# SCH_Octoslime_2022-08-10_Schematics.net
KiCad netlist of a schematic drawn in EasyEDA
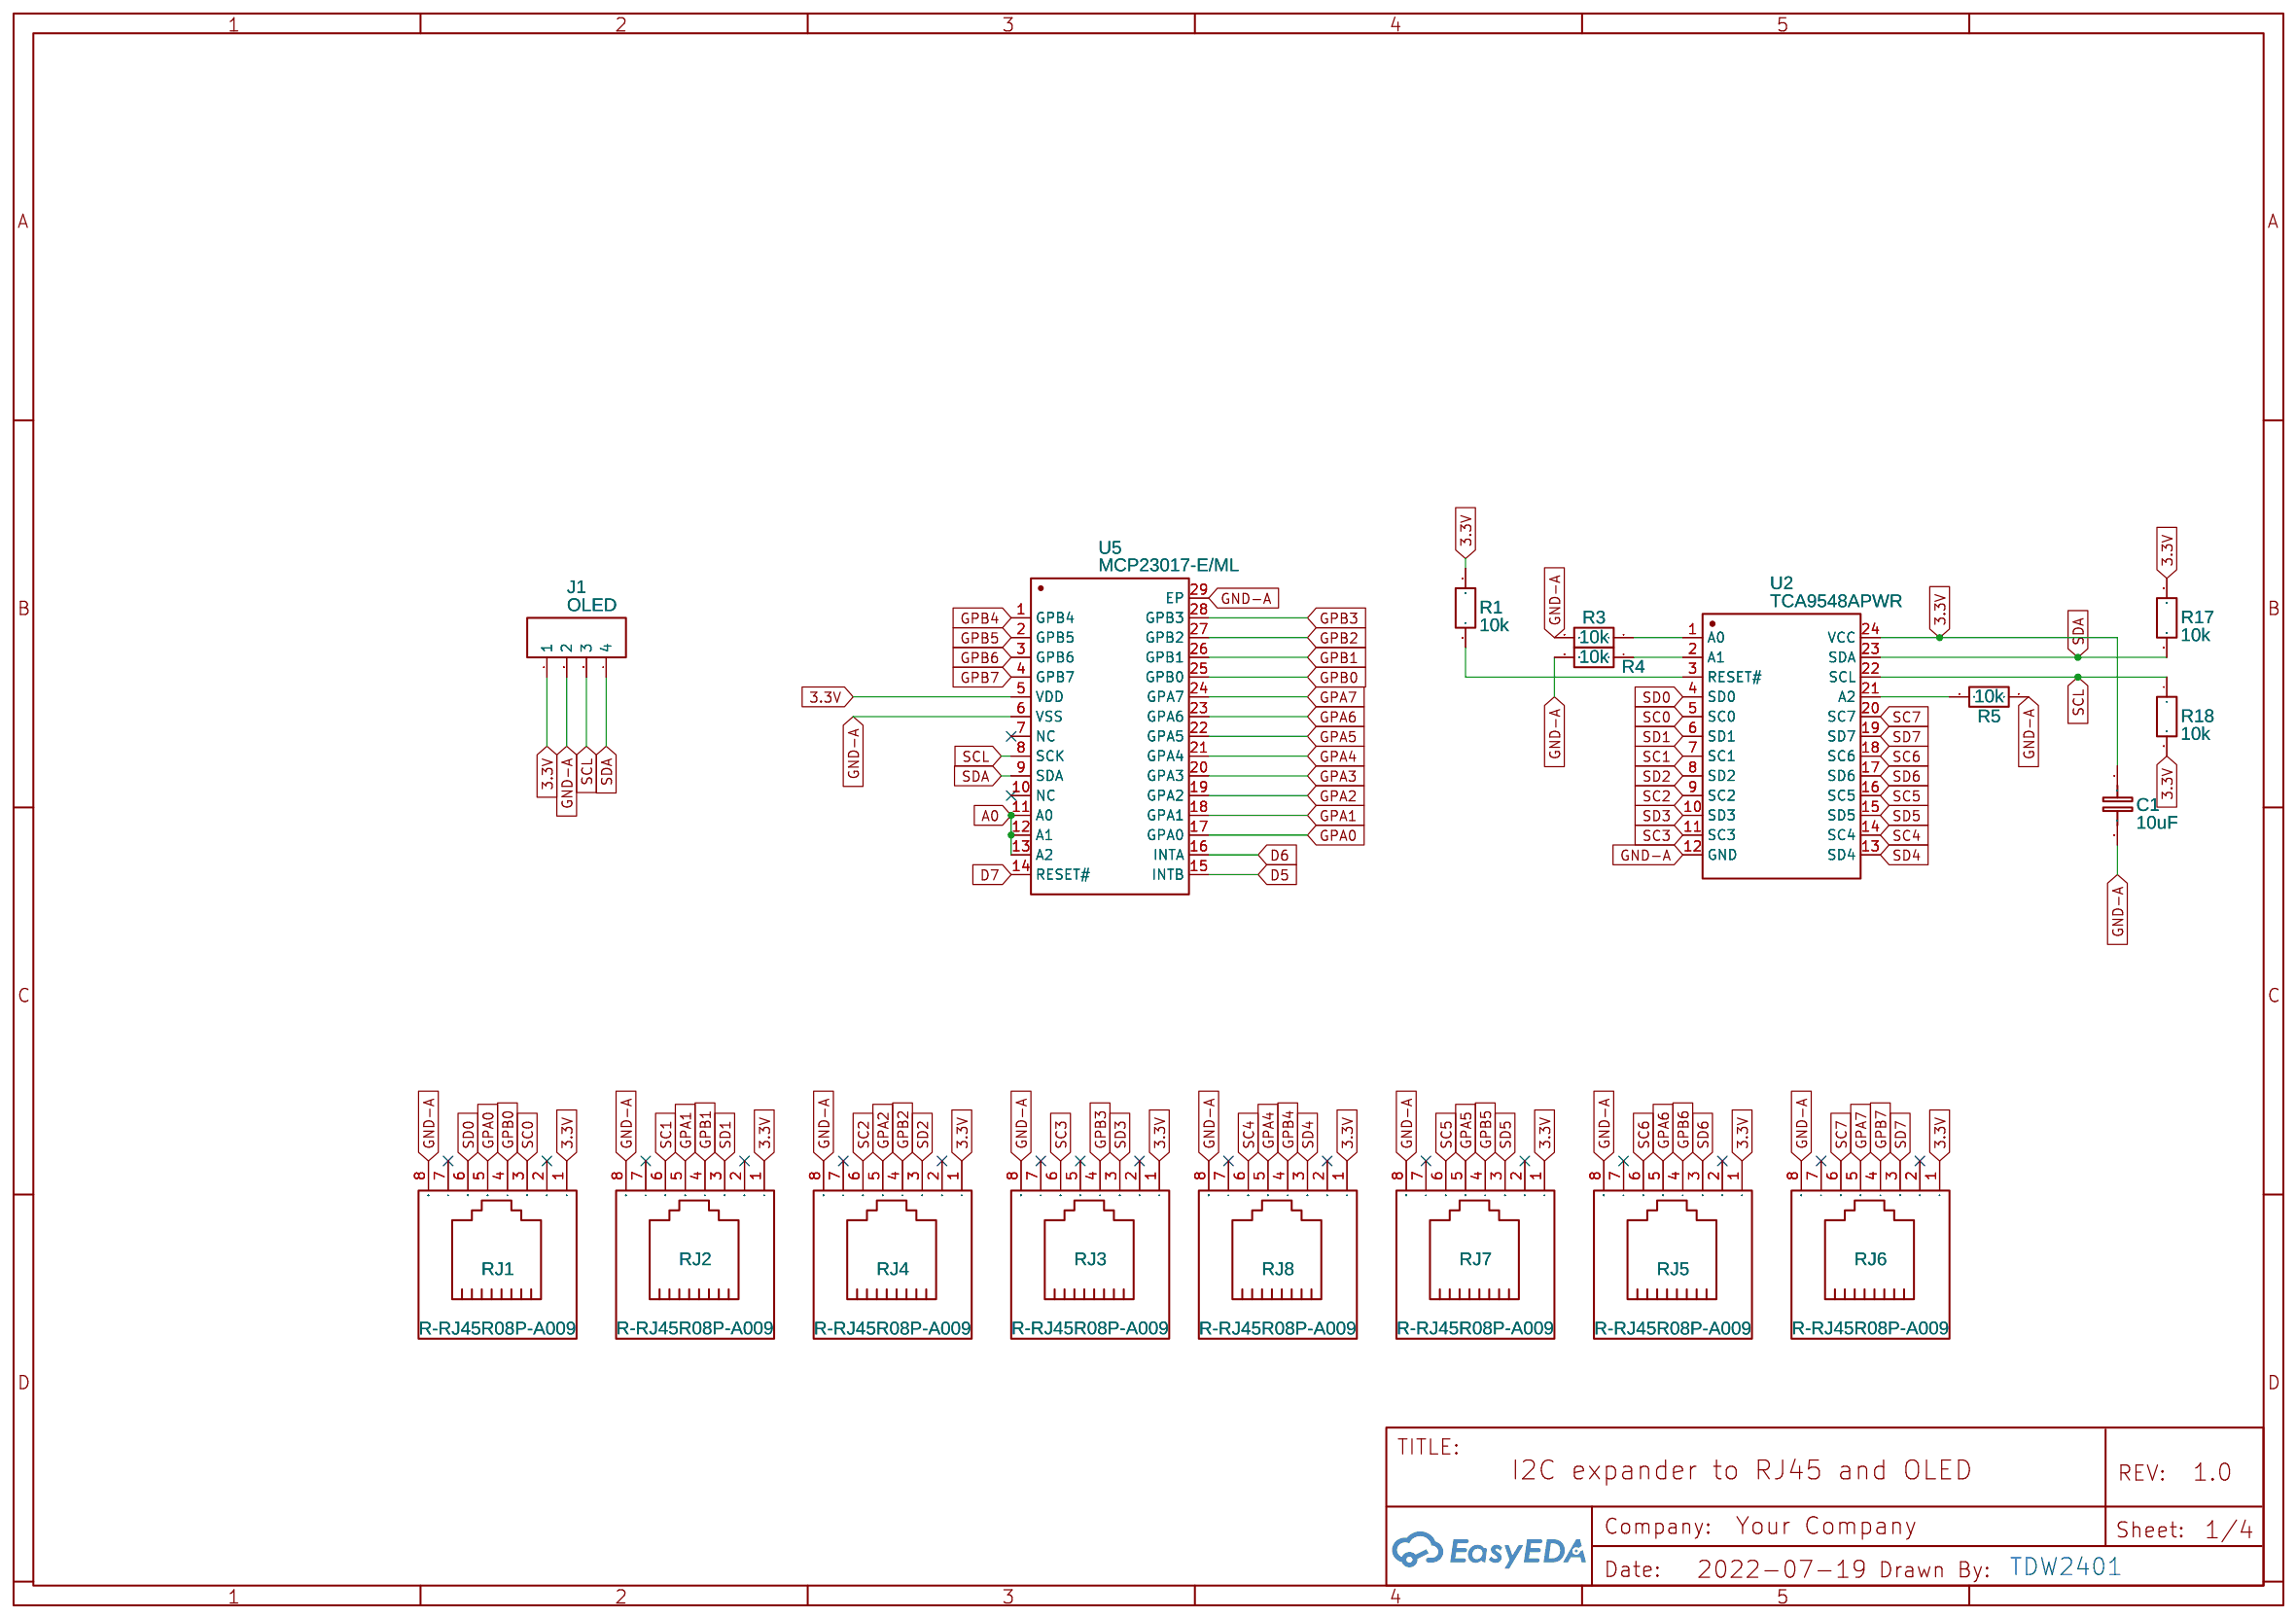
[diagram p0: I2C breakout and OLED]
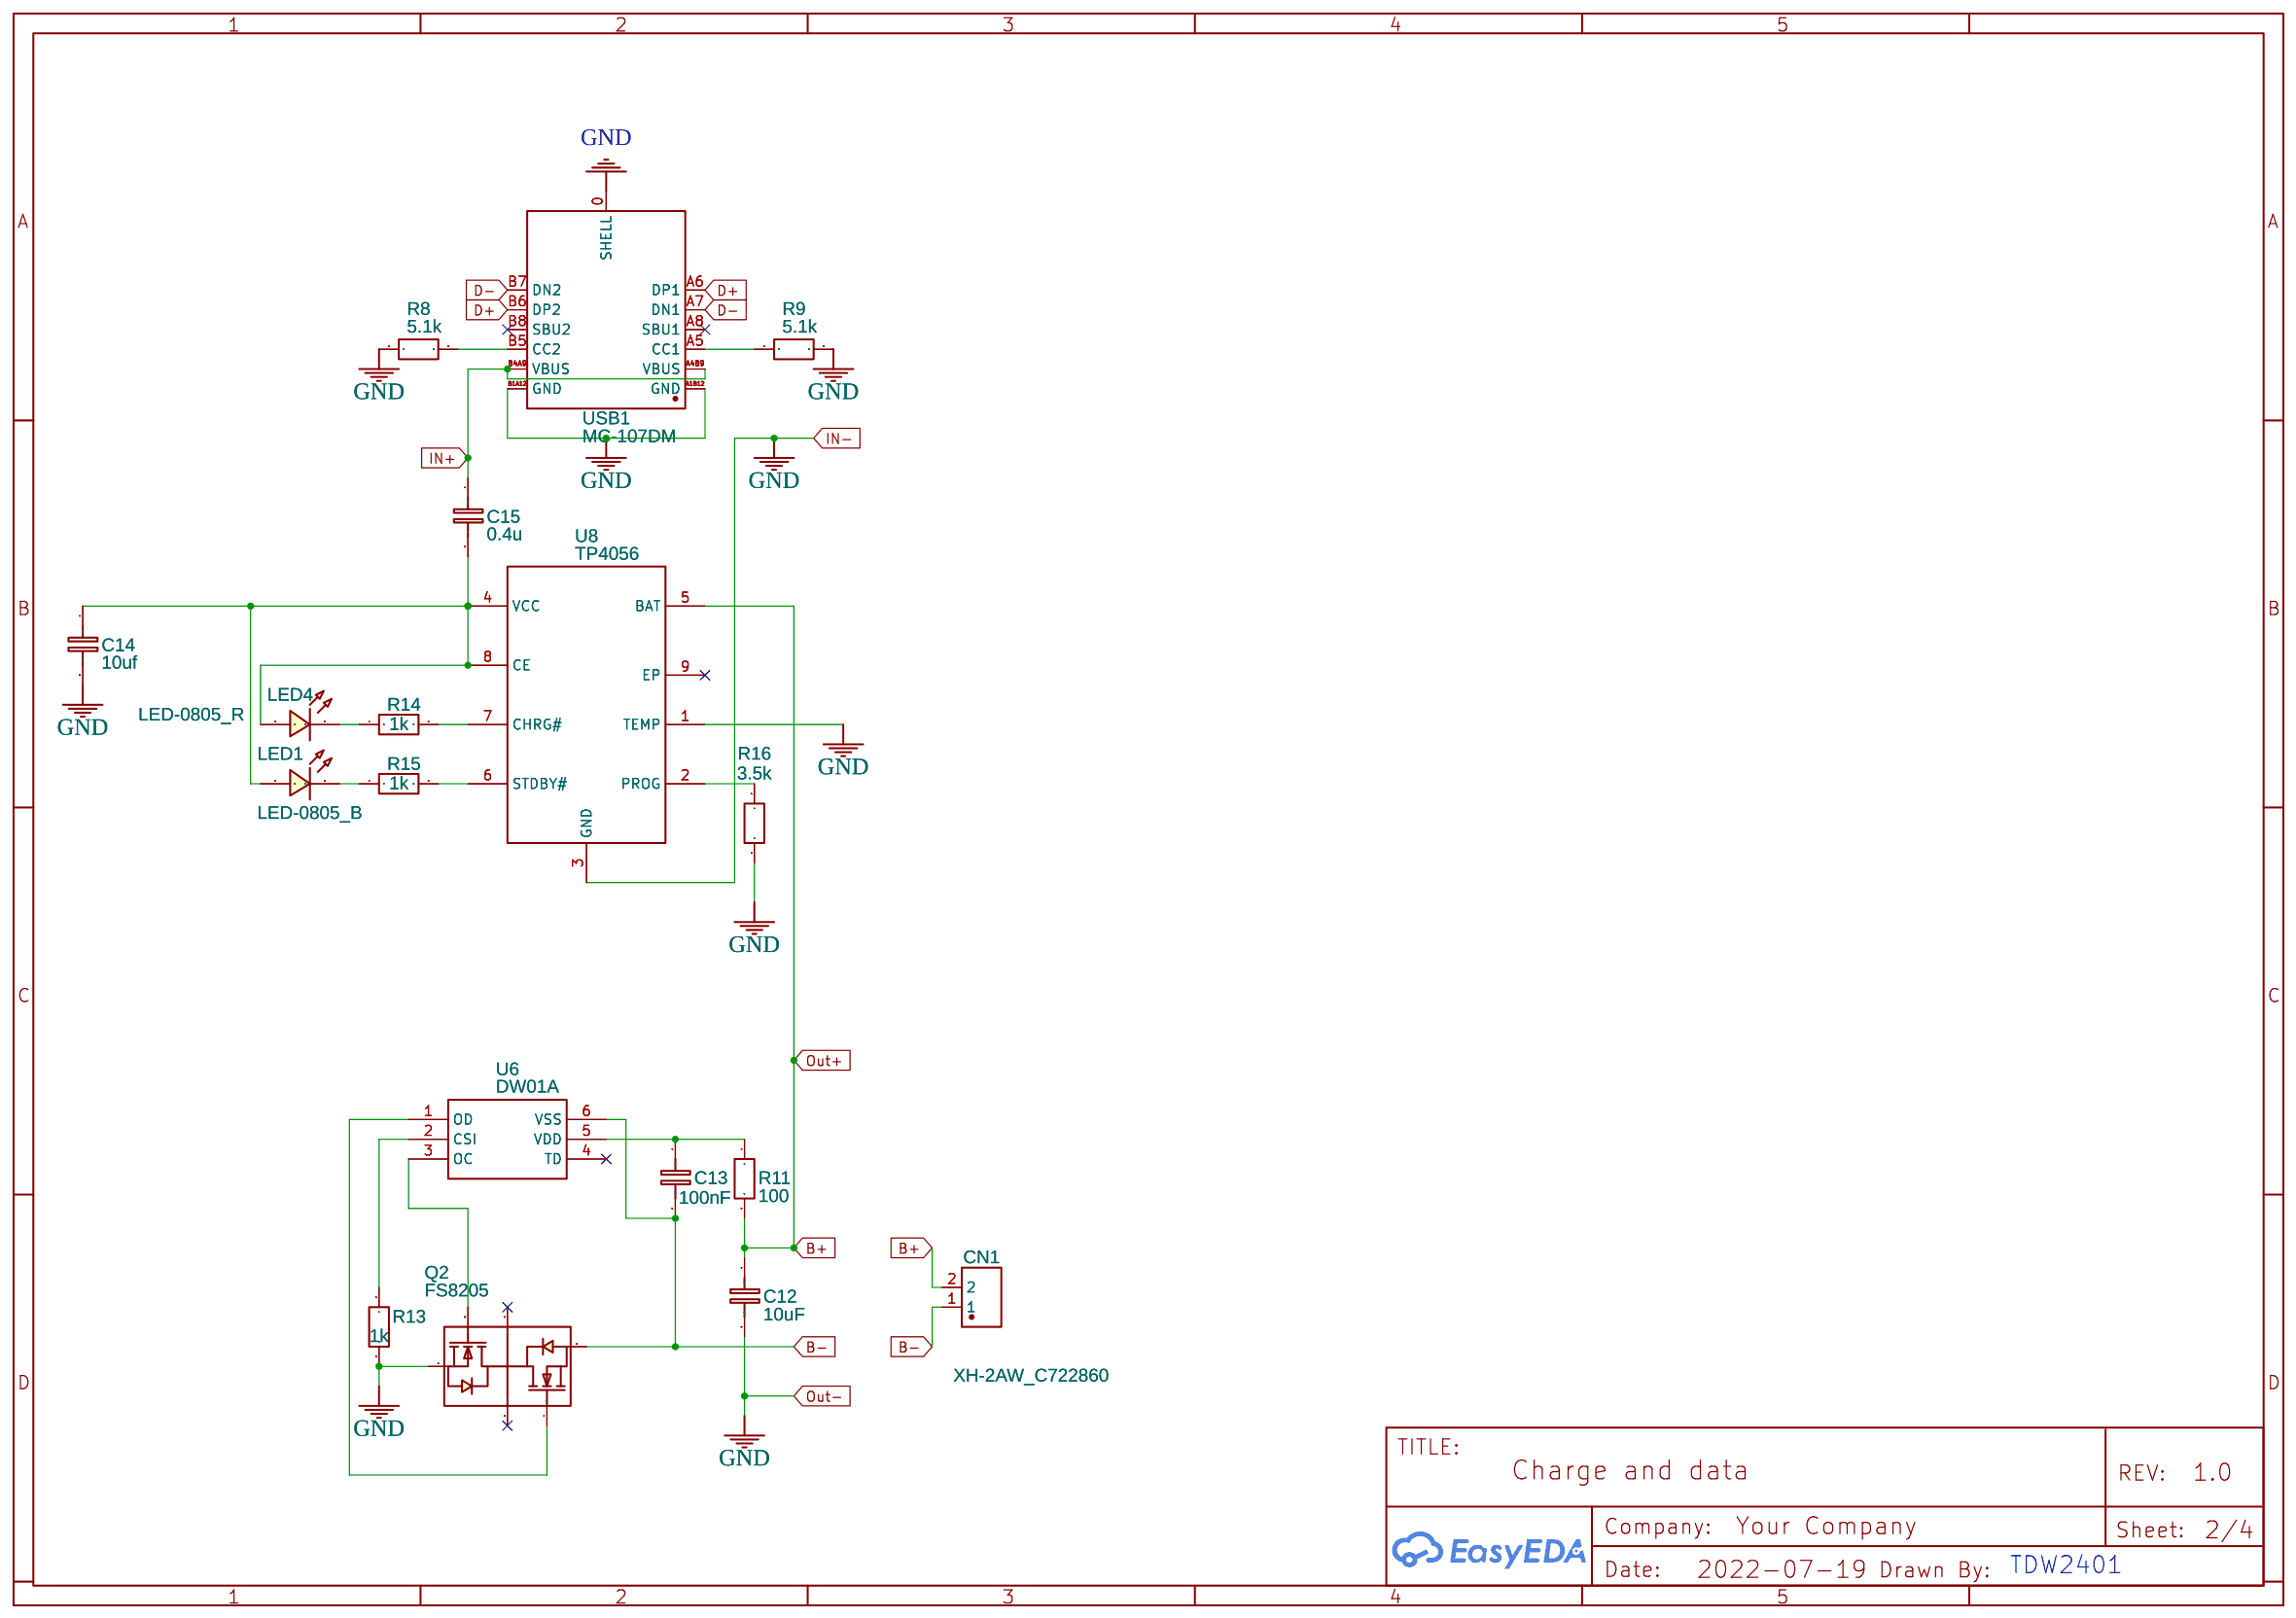
[diagram p1: Charge / data]
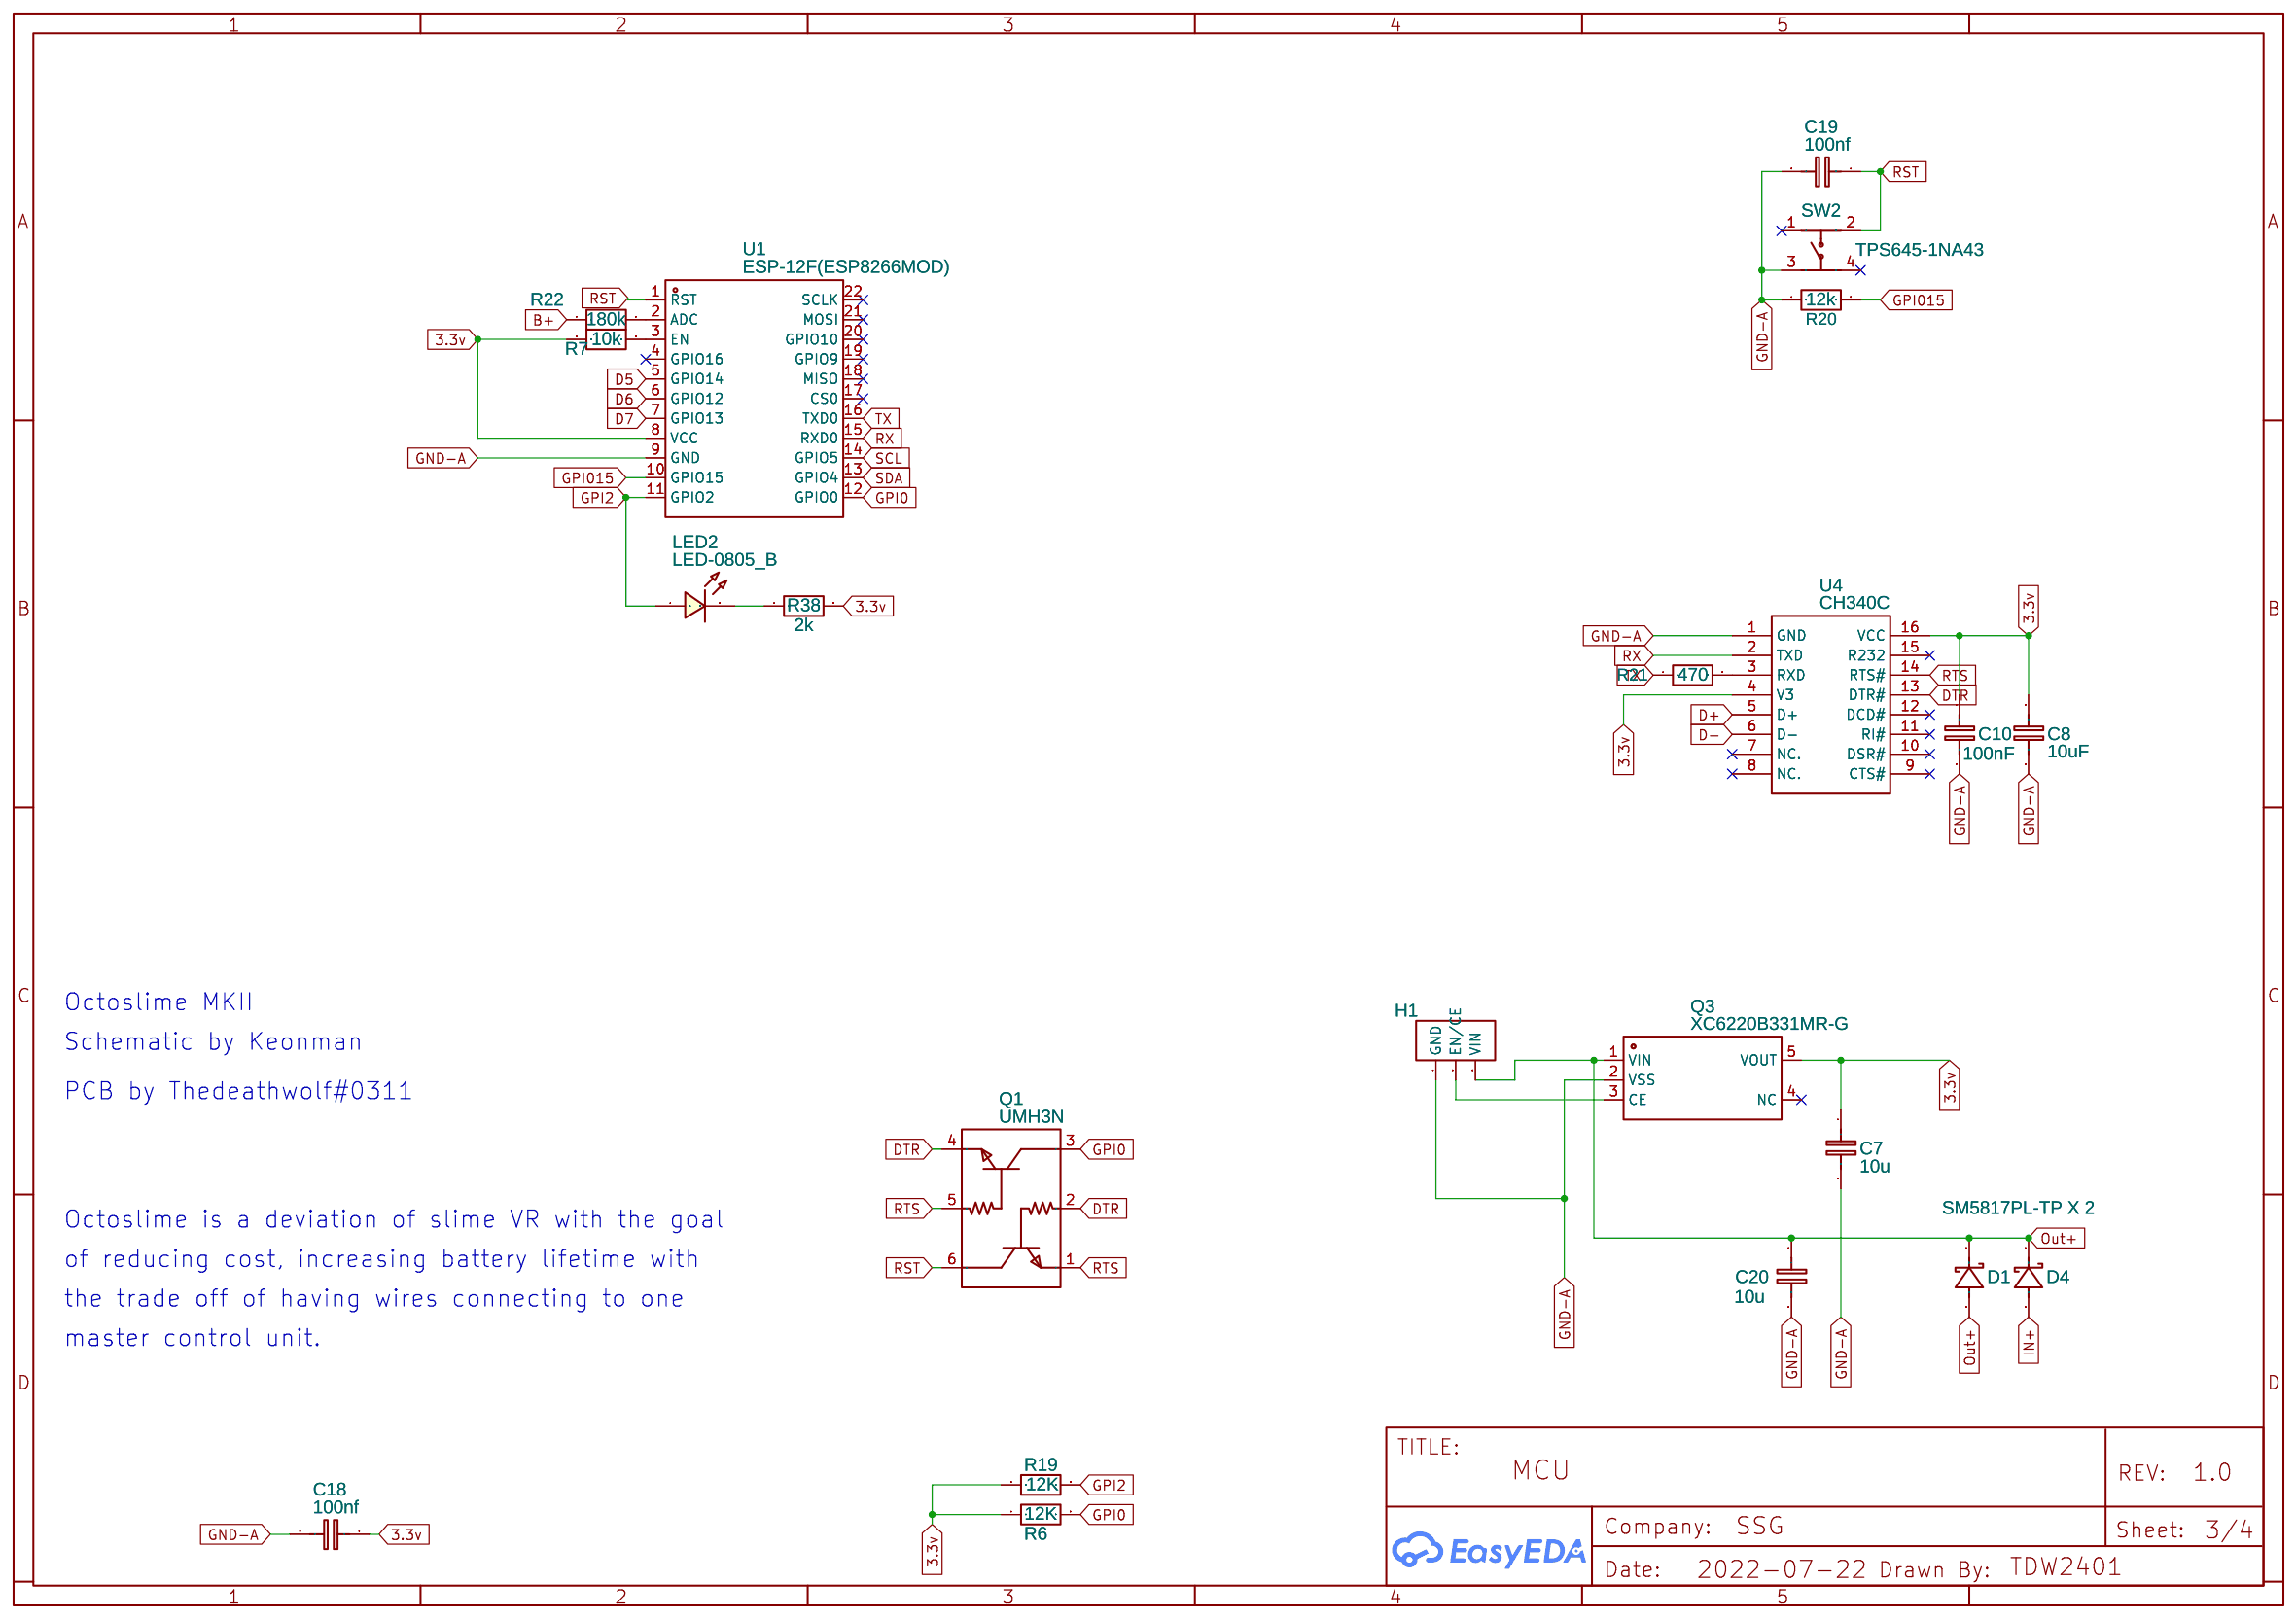
[diagram p2: MCU]
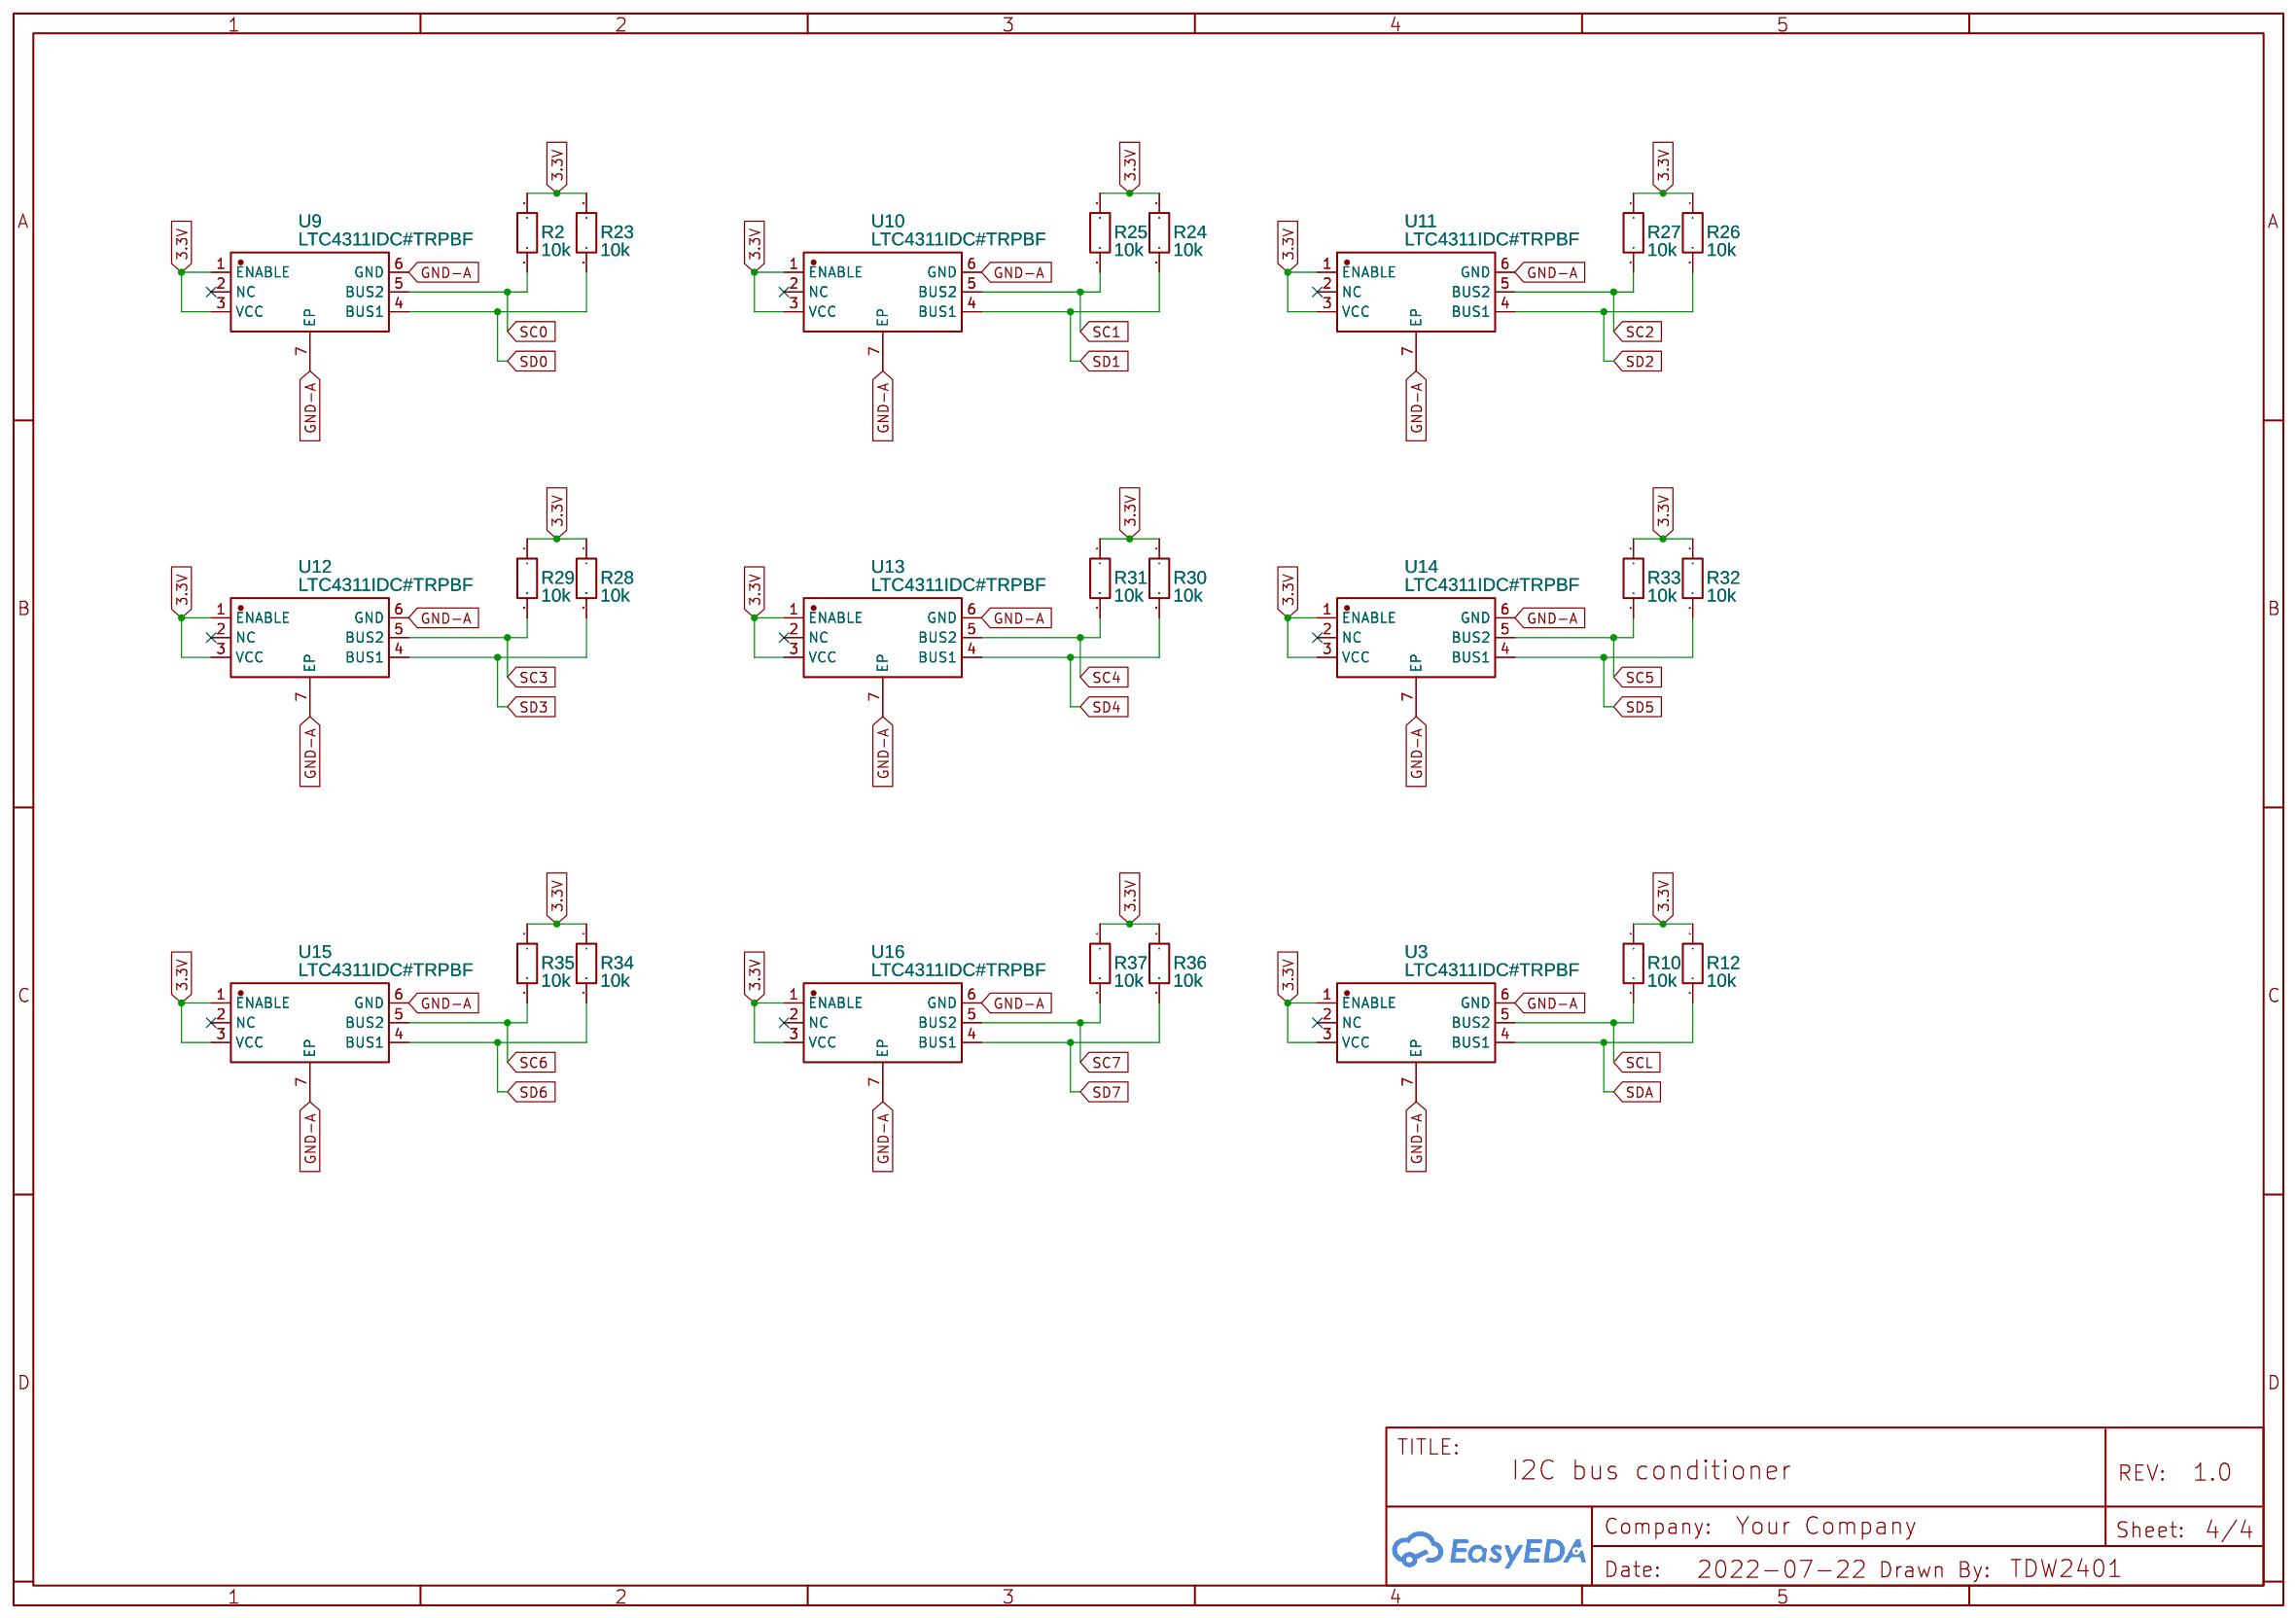
[diagram p3: I2C thing - ma - jigXC6220B331PR-G]

(export (version "E")
  (design (tool "Eeschema 10.0.6"))
  (components
    (comp (ref "C1") (value "10uF") (libsource (lib "") (part "C_0805_EU")))
    (comp (ref "J1")
      (value "OLED")
      (fields (field (name "BOM_Supplier Part") "C124378"))
      (libsource (lib "") (part "HDR-M-2.54_1x4"))
    )
    (comp (ref "R1") (value "10k") (libsource (lib "") (part "R_0805_EU")))
    (comp (ref "R3") (value "10k") (libsource (lib "") (part "R_0805_EU_1")))
    (comp (ref "R4") (value "10k") (libsource (lib "") (part "R_0805_EU_1")))
    (comp (ref "R5") (value "10k") (libsource (lib "") (part "R_0805_EU_1")))
    (comp (ref "R17") (value "10k") (libsource (lib "") (part "R_0805_EU")))
    (comp (ref "R18") (value "10k") (libsource (lib "") (part "R_0805_EU")))
    (comp (ref "RJ1")
      (value "R-RJ45R08P-A009")
      (fields (field (name "BOM_Supplier Part") "C2902700"))
      (libsource (lib "") (part "R-RJ45R08P-A009"))
    )
    (comp (ref "RJ2")
      (value "R-RJ45R08P-A009")
      (fields (field (name "BOM_Supplier Part") "C2902700"))
      (libsource (lib "") (part "R-RJ45R08P-A009"))
    )
    (comp (ref "RJ3")
      (value "R-RJ45R08P-A009")
      (fields (field (name "BOM_Supplier Part") "C2902700"))
      (libsource (lib "") (part "R-RJ45R08P-A009"))
    )
    (comp (ref "RJ4")
      (value "R-RJ45R08P-A009")
      (fields (field (name "BOM_Supplier Part") "C2902700"))
      (libsource (lib "") (part "R-RJ45R08P-A009"))
    )
    (comp (ref "RJ5")
      (value "R-RJ45R08P-A009")
      (fields (field (name "BOM_Supplier Part") "C2902700"))
      (libsource (lib "") (part "R-RJ45R08P-A009"))
    )
    (comp (ref "RJ6")
      (value "R-RJ45R08P-A009")
      (fields (field (name "BOM_Supplier Part") "C2902700"))
      (libsource (lib "") (part "R-RJ45R08P-A009"))
    )
    (comp (ref "RJ7")
      (value "R-RJ45R08P-A009")
      (fields (field (name "BOM_Supplier Part") "C2902700"))
      (libsource (lib "") (part "R-RJ45R08P-A009"))
    )
    (comp (ref "RJ8")
      (value "R-RJ45R08P-A009")
      (fields (field (name "BOM_Supplier Part") "C2902700"))
      (libsource (lib "") (part "R-RJ45R08P-A009"))
    )
    (comp (ref "U2")
      (value "TCA9548APWR")
      (fields (field (name "BOM_Supplier Part") "C130026"))
      (libsource (lib "") (part "TCA9548APWR"))
    )
    (comp (ref "U5")
      (value "MCP23017-E/ML")
      (fields (field (name "BOM_Supplier Part") "C639770"))
      (libsource (lib "") (part "MCP23017-E/ML"))
    )
    (comp (ref "C12") (value "10uF") (libsource (lib "") (part "C_0805_EU_1")))
    (comp (ref "C13") (value "100nF") (libsource (lib "") (part "C_0805_EU_1")))
    (comp (ref "C14") (value "10uf") (libsource (lib "") (part "C_0805_EU_2")))
    (comp (ref "C15") (value "0.4u") (libsource (lib "") (part "C_0805_EU")))
    (comp (ref "CN1")
      (value "XH-2AW_C722860")
      (fields (field (name "BOM_Manufacturer Part") "XH-2AW") (field (name "BOM_Supplier Part") "C722860"))
      (libsource (lib "") (part "XH-2AW_C722860"))
    )
    (comp (ref "LED1")
      (value "LED-0805_B")
      (fields
        (field (name "BOM_Manufacturer Part") "D-B080508B1-KS2")
        (field (name "BOM_Supplier Part") "C108412")
      )
      (libsource (lib "") (part "LED-0805_B"))
    )
    (comp (ref "LED4")
      (value "LED-0805_R")
      (fields
        (field (name "BOM_Manufacturer Part") "17-21SURC/S530-A3/TR8")
        (field (name "BOM_Supplier Part") "C72037")
      )
      (libsource (lib "") (part "LED-0805_R"))
    )
    (comp (ref "Q2")
      (value "FS8205")
      (fields (field (name "BOM_Supplier Part") "C32254"))
      (libsource (lib "") (part "FS8205"))
    )
    (comp (ref "R8") (value "5.1k") (libsource (lib "") (part "R_0805_EU_1")))
    (comp (ref "R9") (value "5.1k") (libsource (lib "") (part "R_0805_EU_1")))
    (comp (ref "R11") (value "100") (libsource (lib "") (part "R_0805_EU")))
    (comp (ref "R13") (value "1k") (libsource (lib "") (part "R_0805_EU")))
    (comp (ref "R14") (value "1k") (libsource (lib "") (part "R_0805_EU_1")))
    (comp (ref "R15") (value "1k") (libsource (lib "") (part "R_0805_EU_1")))
    (comp (ref "R16") (value "3.5k") (libsource (lib "") (part "R_0805_EU")))
    (comp (ref "U6")
      (value "DW01A")
      (fields (field (name "BOM_Supplier Part") "C85680"))
      (libsource (lib "") (part "DW01A"))
    )
    (comp (ref "U8")
      (value "TP4056")
      (fields (field (name "BOM_Supplier Part") "C16581"))
      (libsource (lib "") (part "TP4056"))
    )
    (comp (ref "USB1")
      (value "MC-107DM")
      (fields (field (name "BOM_Supplier Part") "C2874569"))
      (libsource (lib "") (part "MC-107DM"))
    )
    (comp (ref "C7") (value "10u") (libsource (lib "") (part "C_0805_EU")))
    (comp (ref "C8") (value "10uF") (libsource (lib "") (part "C_0805_EU")))
    (comp (ref "C10") (value "100nF") (libsource (lib "") (part "C_0805_EU")))
    (comp (ref "C18") (value "100nf") (libsource (lib "") (part "C_0805_EU_2")))
    (comp (ref "C19") (value "100nf") (libsource (lib "") (part "C_0805_EU_1")))
    (comp (ref "C20") (value "10u") (libsource (lib "") (part "C_0805_EU")))
    (comp (ref "D1")
      (value "SM5817PL-TP X 2")
      (fields
        (field (name "BOM_Manufacturer Part") "SM5817PL-TP")
        (field (name "BOM_Supplier Part") "C669022")
      )
      (libsource (lib "") (part "SM5817PL-TP"))
    )
    (comp (ref "D4")
      (value "SM5817PL-TP X 2")
      (fields
        (field (name "BOM_Manufacturer Part") "SM5817PL-TP")
        (field (name "BOM_Supplier Part") "C669022")
      )
      (libsource (lib "") (part "SM5817PL-TP"))
    )
    (comp (ref "H1")
      (value "HDR-F-2.54_1x3")
      (fields (field (name "BOM_Supplier Part") "C146690"))
      (libsource (lib "") (part "HDR-F-2.54_1x3"))
    )
    (comp (ref "LED2")
      (value "LED-0805_B")
      (fields
        (field (name "BOM_Manufacturer Part") "D-B080508B1-KS2")
        (field (name "BOM_Supplier Part") "C108412")
      )
      (libsource (lib "") (part "LED-0805_B"))
    )
    (comp (ref "Q1")
      (value "UMH3N")
      (fields (field (name "BOM_Supplier Part") "C62892"))
      (libsource (lib "") (part "UMH3N"))
    )
    (comp (ref "Q3")
      (value "XC6220B331MR-G")
      (fields (field (name "BOM_Supplier Part") "C86534"))
      (libsource (lib "") (part "XC6220B331MR-G"))
    )
    (comp (ref "R6") (value "12K") (libsource (lib "") (part "R_0805_EU")))
    (comp (ref "R7") (value "10k") (libsource (lib "") (part "R_0805_EU")))
    (comp (ref "R19") (value "12K") (libsource (lib "") (part "R_0805_EU")))
    (comp (ref "R20") (value "12k") (libsource (lib "") (part "R_0805_EU")))
    (comp (ref "R21") (value "470") (libsource (lib "") (part "R_0805_EU")))
    (comp (ref "R22") (value "180k") (libsource (lib "") (part "R_0805_EU")))
    (comp (ref "R38") (value "2k") (libsource (lib "") (part "R_0805_EU")))
    (comp (ref "SW2")
      (value "TPS645-1NA43")
      (fields (field (name "BOM_Supplier Part") "C2828575"))
      (libsource (lib "") (part "TPS645-1NA43"))
    )
    (comp (ref "U1")
      (value "ESP-12F(ESP8266MOD)")
      (fields (field (name "BOM_Supplier Part") "C82891"))
      (libsource (lib "") (part "ESP-12F(ESP8266MOD)"))
    )
    (comp (ref "U4")
      (value "CH340C")
      (fields (field (name "BOM_Supplier Part") "C84681"))
      (libsource (lib "") (part "CH340C"))
    )
    (comp (ref "R2") (value "10k") (libsource (lib "") (part "R_0805_EU")))
    (comp (ref "R10") (value "10k") (libsource (lib "") (part "R_0805_EU")))
    (comp (ref "R12") (value "10k") (libsource (lib "") (part "R_0805_EU")))
    (comp (ref "R23") (value "10k") (libsource (lib "") (part "R_0805_EU")))
    (comp (ref "R24") (value "10k") (libsource (lib "") (part "R_0805_EU")))
    (comp (ref "R25") (value "10k") (libsource (lib "") (part "R_0805_EU")))
    (comp (ref "R26") (value "10k") (libsource (lib "") (part "R_0805_EU")))
    (comp (ref "R27") (value "10k") (libsource (lib "") (part "R_0805_EU")))
    (comp (ref "R28") (value "10k") (libsource (lib "") (part "R_0805_EU")))
    (comp (ref "R29") (value "10k") (libsource (lib "") (part "R_0805_EU")))
    (comp (ref "R30") (value "10k") (libsource (lib "") (part "R_0805_EU")))
    (comp (ref "R31") (value "10k") (libsource (lib "") (part "R_0805_EU")))
    (comp (ref "R32") (value "10k") (libsource (lib "") (part "R_0805_EU")))
    (comp (ref "R33") (value "10k") (libsource (lib "") (part "R_0805_EU")))
    (comp (ref "R34") (value "10k") (libsource (lib "") (part "R_0805_EU")))
    (comp (ref "R35") (value "10k") (libsource (lib "") (part "R_0805_EU")))
    (comp (ref "R36") (value "10k") (libsource (lib "") (part "R_0805_EU")))
    (comp (ref "R37") (value "10k") (libsource (lib "") (part "R_0805_EU")))
    (comp (ref "U3")
      (value "LTC4311IDC#TRPBF")
      (fields (field (name "BOM_Supplier Part") "C688096"))
      (libsource (lib "") (part "LTC4311IDC#TRPBF"))
    )
    (comp (ref "U9")
      (value "LTC4311IDC#TRPBF")
      (fields (field (name "BOM_Supplier Part") "C688096"))
      (libsource (lib "") (part "LTC4311IDC#TRPBF"))
    )
    (comp (ref "U10")
      (value "LTC4311IDC#TRPBF")
      (fields (field (name "BOM_Supplier Part") "C688096"))
      (libsource (lib "") (part "LTC4311IDC#TRPBF"))
    )
    (comp (ref "U11")
      (value "LTC4311IDC#TRPBF")
      (fields (field (name "BOM_Supplier Part") "C688096"))
      (libsource (lib "") (part "LTC4311IDC#TRPBF"))
    )
    (comp (ref "U12")
      (value "LTC4311IDC#TRPBF")
      (fields (field (name "BOM_Supplier Part") "C688096"))
      (libsource (lib "") (part "LTC4311IDC#TRPBF"))
    )
    (comp (ref "U13")
      (value "LTC4311IDC#TRPBF")
      (fields (field (name "BOM_Supplier Part") "C688096"))
      (libsource (lib "") (part "LTC4311IDC#TRPBF"))
    )
    (comp (ref "U14")
      (value "LTC4311IDC#TRPBF")
      (fields (field (name "BOM_Supplier Part") "C688096"))
      (libsource (lib "") (part "LTC4311IDC#TRPBF"))
    )
    (comp (ref "U15")
      (value "LTC4311IDC#TRPBF")
      (fields (field (name "BOM_Supplier Part") "C688096"))
      (libsource (lib "") (part "LTC4311IDC#TRPBF"))
    )
    (comp (ref "U16")
      (value "LTC4311IDC#TRPBF")
      (fields (field (name "BOM_Supplier Part") "C688096"))
      (libsource (lib "") (part "LTC4311IDC#TRPBF"))
    )
  )
  (nets
    (net (code "1") (name "3.3V") (class "Default")
      (node (ref "C1") (pin "1") (pinfunction "1_1") (pintype "unspecified"))
      (node (ref "J1") (pin "1") (pinfunction "1_1") (pintype "unspecified"))
      (node (ref "R1") (pin "1") (pinfunction "1_1") (pintype "unspecified"))
      (node (ref "R10") (pin "1") (pinfunction "1_1") (pintype "unspecified"))
      (node (ref "R12") (pin "1") (pinfunction "1_1") (pintype "unspecified"))
      (node (ref "R17") (pin "1") (pinfunction "1_1") (pintype "unspecified"))
      (node (ref "R18") (pin "2") (pinfunction "2_2") (pintype "unspecified"))
      (node (ref "R2") (pin "1") (pinfunction "1_1") (pintype "unspecified"))
      (node (ref "R23") (pin "1") (pinfunction "1_1") (pintype "unspecified"))
      (node (ref "R24") (pin "1") (pinfunction "1_1") (pintype "unspecified"))
      (node (ref "R25") (pin "1") (pinfunction "1_1") (pintype "unspecified"))
      (node (ref "R26") (pin "1") (pinfunction "1_1") (pintype "unspecified"))
      (node (ref "R27") (pin "1") (pinfunction "1_1") (pintype "unspecified"))
      (node (ref "R28") (pin "1") (pinfunction "1_1") (pintype "unspecified"))
      (node (ref "R29") (pin "1") (pinfunction "1_1") (pintype "unspecified"))
      (node (ref "R30") (pin "1") (pinfunction "1_1") (pintype "unspecified"))
      (node (ref "R31") (pin "1") (pinfunction "1_1") (pintype "unspecified"))
      (node (ref "R32") (pin "1") (pinfunction "1_1") (pintype "unspecified"))
      (node (ref "R33") (pin "1") (pinfunction "1_1") (pintype "unspecified"))
      (node (ref "R34") (pin "1") (pinfunction "1_1") (pintype "unspecified"))
      (node (ref "R35") (pin "1") (pinfunction "1_1") (pintype "unspecified"))
      (node (ref "R36") (pin "1") (pinfunction "1_1") (pintype "unspecified"))
      (node (ref "R37") (pin "1") (pinfunction "1_1") (pintype "unspecified"))
      (node (ref "RJ1") (pin "1") (pinfunction "1_1") (pintype "unspecified"))
      (node (ref "RJ2") (pin "1") (pinfunction "1_1") (pintype "unspecified"))
      (node (ref "RJ3") (pin "1") (pinfunction "1_1") (pintype "unspecified"))
      (node (ref "RJ4") (pin "1") (pinfunction "1_1") (pintype "unspecified"))
      (node (ref "RJ5") (pin "1") (pinfunction "1_1") (pintype "unspecified"))
      (node (ref "RJ6") (pin "1") (pinfunction "1_1") (pintype "unspecified"))
      (node (ref "RJ7") (pin "1") (pinfunction "1_1") (pintype "unspecified"))
      (node (ref "RJ8") (pin "1") (pinfunction "1_1") (pintype "unspecified"))
      (node (ref "U10") (pin "1") (pinfunction "ENABLE_1") (pintype "unspecified"))
      (node (ref "U10") (pin "3") (pinfunction "VCC_3") (pintype "unspecified"))
      (node (ref "U11") (pin "1") (pinfunction "ENABLE_1") (pintype "unspecified"))
      (node (ref "U11") (pin "3") (pinfunction "VCC_3") (pintype "unspecified"))
      (node (ref "U12") (pin "1") (pinfunction "ENABLE_1") (pintype "unspecified"))
      (node (ref "U12") (pin "3") (pinfunction "VCC_3") (pintype "unspecified"))
      (node (ref "U13") (pin "1") (pinfunction "ENABLE_1") (pintype "unspecified"))
      (node (ref "U13") (pin "3") (pinfunction "VCC_3") (pintype "unspecified"))
      (node (ref "U14") (pin "1") (pinfunction "ENABLE_1") (pintype "unspecified"))
      (node (ref "U14") (pin "3") (pinfunction "VCC_3") (pintype "unspecified"))
      (node (ref "U15") (pin "1") (pinfunction "ENABLE_1") (pintype "unspecified"))
      (node (ref "U15") (pin "3") (pinfunction "VCC_3") (pintype "unspecified"))
      (node (ref "U16") (pin "1") (pinfunction "ENABLE_1") (pintype "unspecified"))
      (node (ref "U16") (pin "3") (pinfunction "VCC_3") (pintype "unspecified"))
      (node (ref "U2") (pin "24") (pinfunction "VCC_24") (pintype "unspecified"))
      (node (ref "U3") (pin "1") (pinfunction "ENABLE_1") (pintype "unspecified"))
      (node (ref "U3") (pin "3") (pinfunction "VCC_3") (pintype "unspecified"))
      (node (ref "U5") (pin "5") (pinfunction "VDD_5") (pintype "unspecified"))
      (node (ref "U9") (pin "1") (pinfunction "ENABLE_1") (pintype "unspecified"))
      (node (ref "U9") (pin "3") (pinfunction "VCC_3") (pintype "unspecified"))
    )
    (net (code "2") (name "3.3v") (class "Default")
      (node (ref "C10") (pin "1") (pinfunction "1_1") (pintype "unspecified"))
      (node (ref "C18") (pin "1") (pinfunction "1_1") (pintype "unspecified"))
      (node (ref "C7") (pin "1") (pinfunction "1_1") (pintype "unspecified"))
      (node (ref "C8") (pin "1") (pinfunction "1_1") (pintype "unspecified"))
      (node (ref "Q3") (pin "5") (pinfunction "VOUT_5") (pintype "unspecified"))
      (node (ref "R19") (pin "1") (pinfunction "1_1") (pintype "unspecified"))
      (node (ref "R38") (pin "2") (pinfunction "2_2") (pintype "unspecified"))
      (node (ref "R6") (pin "1") (pinfunction "1_1") (pintype "unspecified"))
      (node (ref "R7") (pin "1") (pinfunction "1_1") (pintype "unspecified"))
      (node (ref "U1") (pin "8") (pinfunction "VCC_8") (pintype "unspecified"))
      (node (ref "U4") (pin "16") (pinfunction "VCC_16") (pintype "unspecified"))
      (node (ref "U4") (pin "4") (pinfunction "V3_4") (pintype "unspecified"))
    )
    (net (code "3") (name "A0") (class "Default")
      (node (ref "U5") (pin "11") (pinfunction "A0_11") (pintype "unspecified"))
      (node (ref "U5") (pin "12") (pinfunction "A1_12") (pintype "unspecified"))
      (node (ref "U5") (pin "13") (pinfunction "A2_13") (pintype "unspecified"))
    )
    (net (code "4") (name "B+") (class "Default")
      (node (ref "C12") (pin "1") (pinfunction "1_1") (pintype "unspecified"))
      (node (ref "C20") (pin "1") (pinfunction "1_1") (pintype "unspecified"))
      (node (ref "CN1") (pin "2") (pinfunction "2_2") (pintype "unspecified"))
      (node (ref "D1") (pin "1") (pinfunction "C_1") (pintype "unspecified"))
      (node (ref "D1") (pin "2") (pinfunction "A_2") (pintype "unspecified"))
      (node (ref "D4") (pin "1") (pinfunction "C_1") (pintype "unspecified"))
      (node (ref "H1") (pin "3") (pinfunction "VIN_3") (pintype "input"))
      (node (ref "Q3") (pin "1") (pinfunction "VIN_1") (pintype "unspecified"))
      (node (ref "R11") (pin "2") (pinfunction "2_2") (pintype "unspecified"))
      (node (ref "R22") (pin "1") (pinfunction "1_1") (pintype "unspecified"))
      (node (ref "U8") (pin "5") (pinfunction "BAT_5") (pintype "unspecified"))
    )
    (net (code "5") (name "B-") (class "Default")
      (node (ref "C13") (pin "2") (pinfunction "2_2") (pintype "unspecified"))
      (node (ref "CN1") (pin "1") (pinfunction "1_1") (pintype "unspecified"))
      (node (ref "Q2") (pin "3") (pinfunction "S2_3") (pintype "unspecified"))
      (node (ref "U6") (pin "6") (pinfunction "VSS_6") (pintype "unspecified"))
    )
    (net (code "6") (name "D+") (class "Default")
      (node (ref "U4") (pin "5") (pinfunction "D+_5") (pintype "unspecified"))
      (node (ref "USB1") (pin "A6") (pinfunction "DP1_A6") (pintype "unspecified"))
      (node (ref "USB1") (pin "B6") (pinfunction "DP2_B6") (pintype "unspecified"))
    )
    (net (code "7") (name "D-") (class "Default")
      (node (ref "U4") (pin "6") (pinfunction "D-_6") (pintype "unspecified"))
      (node (ref "USB1") (pin "A7") (pinfunction "DN1_A7") (pintype "unspecified"))
      (node (ref "USB1") (pin "B7") (pinfunction "DN2_B7") (pintype "unspecified"))
    )
    (net (code "8") (name "D5") (class "Default")
      (node (ref "U1") (pin "5") (pinfunction "GPIO14_5") (pintype "unspecified"))
      (node (ref "U5") (pin "15") (pinfunction "INTB_15") (pintype "unspecified"))
    )
    (net (code "9") (name "D6") (class "Default")
      (node (ref "U1") (pin "6") (pinfunction "GPIO12_6") (pintype "unspecified"))
      (node (ref "U5") (pin "16") (pinfunction "INTA_16") (pintype "unspecified"))
    )
    (net (code "10") (name "D7") (class "Default")
      (node (ref "U1") (pin "7") (pinfunction "GPIO13_7") (pintype "unspecified"))
      (node (ref "U5") (pin "14") (pinfunction "RESET#_14") (pintype "unspecified"))
    )
    (net (code "11") (name "DTR") (class "Default")
      (node (ref "Q1") (pin "2") (pinfunction "B_2") (pintype "unspecified"))
      (node (ref "Q1") (pin "4") (pinfunction "E_4") (pintype "unspecified"))
      (node (ref "U4") (pin "13") (pinfunction "DTR#_13") (pintype "unspecified"))
    )
    (net (code "12") (name "GND-A") (class "Default")
      (node (ref "C1") (pin "2") (pinfunction "2_2") (pintype "unspecified"))
      (node (ref "C10") (pin "2") (pinfunction "2_2") (pintype "unspecified"))
      (node (ref "C18") (pin "2") (pinfunction "2_2") (pintype "unspecified"))
      (node (ref "C19") (pin "2") (pinfunction "2_2") (pintype "unspecified"))
      (node (ref "C20") (pin "2") (pinfunction "2_2") (pintype "unspecified"))
      (node (ref "C7") (pin "2") (pinfunction "2_2") (pintype "unspecified"))
      (node (ref "C8") (pin "2") (pinfunction "2_2") (pintype "unspecified"))
      (node (ref "H1") (pin "1") (pinfunction "GND_1") (pintype "input"))
      (node (ref "J1") (pin "2") (pinfunction "2_2") (pintype "unspecified"))
      (node (ref "Q3") (pin "2") (pinfunction "VSS_2") (pintype "unspecified"))
      (node (ref "R20") (pin "1") (pinfunction "1_1") (pintype "unspecified"))
      (node (ref "R3") (pin "2") (pinfunction "2_2") (pintype "unspecified"))
      (node (ref "R4") (pin "2") (pinfunction "2_2") (pintype "unspecified"))
      (node (ref "R5") (pin "1") (pinfunction "1_1") (pintype "unspecified"))
      (node (ref "RJ1") (pin "8") (pinfunction "8_8") (pintype "unspecified"))
      (node (ref "RJ2") (pin "8") (pinfunction "8_8") (pintype "unspecified"))
      (node (ref "RJ3") (pin "8") (pinfunction "8_8") (pintype "unspecified"))
      (node (ref "RJ4") (pin "8") (pinfunction "8_8") (pintype "unspecified"))
      (node (ref "RJ5") (pin "8") (pinfunction "8_8") (pintype "unspecified"))
      (node (ref "RJ6") (pin "8") (pinfunction "8_8") (pintype "unspecified"))
      (node (ref "RJ7") (pin "8") (pinfunction "8_8") (pintype "unspecified"))
      (node (ref "RJ8") (pin "8") (pinfunction "8_8") (pintype "unspecified"))
      (node (ref "SW2") (pin "3") (pinfunction "3_3") (pintype "unspecified"))
      (node (ref "U1") (pin "9") (pinfunction "GND_9") (pintype "unspecified"))
      (node (ref "U10") (pin "6") (pinfunction "GND_6") (pintype "unspecified"))
      (node (ref "U10") (pin "7") (pinfunction "EP_7") (pintype "unspecified"))
      (node (ref "U11") (pin "6") (pinfunction "GND_6") (pintype "unspecified"))
      (node (ref "U11") (pin "7") (pinfunction "EP_7") (pintype "unspecified"))
      (node (ref "U12") (pin "6") (pinfunction "GND_6") (pintype "unspecified"))
      (node (ref "U12") (pin "7") (pinfunction "EP_7") (pintype "unspecified"))
      (node (ref "U13") (pin "6") (pinfunction "GND_6") (pintype "unspecified"))
      (node (ref "U13") (pin "7") (pinfunction "EP_7") (pintype "unspecified"))
      (node (ref "U14") (pin "6") (pinfunction "GND_6") (pintype "unspecified"))
      (node (ref "U14") (pin "7") (pinfunction "EP_7") (pintype "unspecified"))
      (node (ref "U15") (pin "6") (pinfunction "GND_6") (pintype "unspecified"))
      (node (ref "U15") (pin "7") (pinfunction "EP_7") (pintype "unspecified"))
      (node (ref "U16") (pin "6") (pinfunction "GND_6") (pintype "unspecified"))
      (node (ref "U16") (pin "7") (pinfunction "EP_7") (pintype "unspecified"))
      (node (ref "U2") (pin "12") (pinfunction "GND_12") (pintype "unspecified"))
      (node (ref "U3") (pin "6") (pinfunction "GND_6") (pintype "unspecified"))
      (node (ref "U3") (pin "7") (pinfunction "EP_7") (pintype "unspecified"))
      (node (ref "U4") (pin "1") (pinfunction "GND_1") (pintype "unspecified"))
      (node (ref "U5") (pin "29") (pinfunction "EP_29") (pintype "unspecified"))
      (node (ref "U5") (pin "6") (pinfunction "VSS_6") (pintype "unspecified"))
      (node (ref "U9") (pin "6") (pinfunction "GND_6") (pintype "unspecified"))
      (node (ref "U9") (pin "7") (pinfunction "EP_7") (pintype "unspecified"))
    )
    (net (code "13") (name "GPA0") (class "Default")
      (node (ref "RJ1") (pin "5") (pinfunction "5_5") (pintype "unspecified"))
      (node (ref "U5") (pin "17") (pinfunction "GPA0_17") (pintype "unspecified"))
    )
    (net (code "14") (name "GPA1") (class "Default")
      (node (ref "RJ2") (pin "5") (pinfunction "5_5") (pintype "unspecified"))
      (node (ref "U5") (pin "18") (pinfunction "GPA1_18") (pintype "unspecified"))
    )
    (net (code "15") (name "GPA2") (class "Default")
      (node (ref "RJ4") (pin "5") (pinfunction "5_5") (pintype "unspecified"))
      (node (ref "U5") (pin "19") (pinfunction "GPA2_19") (pintype "unspecified"))
    )
    (net (code "16") (name "GPA3") (class "Default")
      (node (ref "U5") (pin "20") (pinfunction "GPA3_20") (pintype "unspecified"))
    )
    (net (code "17") (name "GPA4") (class "Default")
      (node (ref "RJ8") (pin "5") (pinfunction "5_5") (pintype "unspecified"))
      (node (ref "U5") (pin "21") (pinfunction "GPA4_21") (pintype "unspecified"))
    )
    (net (code "18") (name "GPA5") (class "Default")
      (node (ref "RJ7") (pin "5") (pinfunction "5_5") (pintype "unspecified"))
      (node (ref "U5") (pin "22") (pinfunction "GPA5_22") (pintype "unspecified"))
    )
    (net (code "19") (name "GPA6") (class "Default")
      (node (ref "RJ5") (pin "5") (pinfunction "5_5") (pintype "unspecified"))
      (node (ref "U5") (pin "23") (pinfunction "GPA6_23") (pintype "unspecified"))
    )
    (net (code "20") (name "GPA7") (class "Default")
      (node (ref "RJ6") (pin "5") (pinfunction "5_5") (pintype "unspecified"))
      (node (ref "U5") (pin "24") (pinfunction "GPA7_24") (pintype "unspecified"))
    )
    (net (code "21") (name "GPB0") (class "Default")
      (node (ref "RJ1") (pin "4") (pinfunction "4_4") (pintype "unspecified"))
      (node (ref "U5") (pin "25") (pinfunction "GPB0_25") (pintype "unspecified"))
    )
    (net (code "22") (name "GPB1") (class "Default")
      (node (ref "RJ2") (pin "4") (pinfunction "4_4") (pintype "unspecified"))
      (node (ref "U5") (pin "26") (pinfunction "GPB1_26") (pintype "unspecified"))
    )
    (net (code "23") (name "GPB2") (class "Default")
      (node (ref "RJ4") (pin "4") (pinfunction "4_4") (pintype "unspecified"))
      (node (ref "U5") (pin "27") (pinfunction "GPB2_27") (pintype "unspecified"))
    )
    (net (code "24") (name "GPB3") (class "Default")
      (node (ref "RJ3") (pin "4") (pinfunction "4_4") (pintype "unspecified"))
      (node (ref "U5") (pin "28") (pinfunction "GPB3_28") (pintype "unspecified"))
    )
    (net (code "25") (name "GPB4") (class "Default")
      (node (ref "RJ8") (pin "4") (pinfunction "4_4") (pintype "unspecified"))
      (node (ref "U5") (pin "1") (pinfunction "GPB4_1") (pintype "unspecified"))
    )
    (net (code "26") (name "GPB5") (class "Default")
      (node (ref "RJ7") (pin "4") (pinfunction "4_4") (pintype "unspecified"))
      (node (ref "U5") (pin "2") (pinfunction "GPB5_2") (pintype "unspecified"))
    )
    (net (code "27") (name "GPB6") (class "Default")
      (node (ref "RJ5") (pin "4") (pinfunction "4_4") (pintype "unspecified"))
      (node (ref "U5") (pin "3") (pinfunction "GPB6_3") (pintype "unspecified"))
    )
    (net (code "28") (name "GPB7") (class "Default")
      (node (ref "RJ6") (pin "4") (pinfunction "4_4") (pintype "unspecified"))
      (node (ref "U5") (pin "4") (pinfunction "GPB7_4") (pintype "unspecified"))
    )
    (net (code "29") (name "GPI0") (class "Default")
      (node (ref "Q1") (pin "3") (pinfunction "C_3") (pintype "unspecified"))
      (node (ref "R6") (pin "2") (pinfunction "2_2") (pintype "unspecified"))
      (node (ref "U1") (pin "12") (pinfunction "GPIO0_12") (pintype "unspecified"))
    )
    (net (code "30") (name "GPI2") (class "Default")
      (node (ref "LED2") (pin "1") (pinfunction "1_1") (pintype "unspecified"))
      (node (ref "R19") (pin "2") (pinfunction "2_2") (pintype "unspecified"))
      (node (ref "U1") (pin "11") (pinfunction "GPIO2_11") (pintype "unspecified"))
    )
    (net (code "31") (name "GPI015") (class "Default")
      (node (ref "R20") (pin "2") (pinfunction "2_2") (pintype "unspecified"))
      (node (ref "U1") (pin "10") (pinfunction "GPIO15_10") (pintype "unspecified"))
    )
    (net (code "32") (name "IN+") (class "Default")
      (node (ref "C15") (pin "1") (pinfunction "1_1") (pintype "unspecified"))
      (node (ref "D4") (pin "2") (pinfunction "A_2") (pintype "unspecified"))
      (node (ref "USB1") (pin "A4B9") (pinfunction "VBUS_A4B9") (pintype "unspecified"))
      (node (ref "USB1") (pin "B4A9") (pinfunction "VBUS_B4A9") (pintype "unspecified"))
    )
    (net (code "33") (name "IN-") (class "Default")
      (node (ref "C12") (pin "2") (pinfunction "2_2") (pintype "unspecified"))
      (node (ref "C14") (pin "2") (pinfunction "2_2") (pintype "unspecified"))
      (node (ref "Q2") (pin "1") (pinfunction "S1_1") (pintype "unspecified"))
      (node (ref "R13") (pin "2") (pinfunction "2_2") (pintype "unspecified"))
      (node (ref "R16") (pin "2") (pinfunction "2_2") (pintype "unspecified"))
      (node (ref "R8") (pin "1") (pinfunction "1_1") (pintype "unspecified"))
      (node (ref "R9") (pin "2") (pinfunction "2_2") (pintype "unspecified"))
      (node (ref "U8") (pin "1") (pinfunction "TEMP_1") (pintype "unspecified"))
      (node (ref "U8") (pin "3") (pinfunction "GND_3") (pintype "unspecified"))
      (node (ref "USB1") (pin "0") (pinfunction "SHELL_0") (pintype "unspecified"))
      (node (ref "USB1") (pin "A1B12") (pinfunction "GND_A1B12") (pintype "unspecified"))
      (node (ref "USB1") (pin "B1A12") (pinfunction "GND_B1A12") (pintype "unspecified"))
    )
    (net (code "34") (name "Net-(H1-EN{slash}CE)") (class "Default")
      (node (ref "H1") (pin "2") (pinfunction "EN/CE_2") (pintype "input"))
      (node (ref "Q3") (pin "3") (pinfunction "CE_3") (pintype "unspecified"))
    )
    (net (code "35") (name "Net-(LED1-Pad2)") (class "Default")
      (node (ref "LED1") (pin "2") (pinfunction "2_2") (pintype "unspecified"))
      (node (ref "R15") (pin "1") (pinfunction "1_1") (pintype "unspecified"))
    )
    (net (code "36") (name "Net-(LED2-Pad2)") (class "Default")
      (node (ref "LED2") (pin "2") (pinfunction "2_2") (pintype "unspecified"))
      (node (ref "R38") (pin "1") (pinfunction "1_1") (pintype "unspecified"))
    )
    (net (code "37") (name "Net-(LED4-Pad2)") (class "Default")
      (node (ref "LED4") (pin "2") (pinfunction "2_2") (pintype "unspecified"))
      (node (ref "R14") (pin "1") (pinfunction "1_1") (pintype "unspecified"))
    )
    (net (code "38") (name "Net-(Q2-G1)") (class "Default")
      (node (ref "Q2") (pin "6") (pinfunction "G1_6") (pintype "unspecified"))
      (node (ref "U6") (pin "3") (pinfunction "OC_3") (pintype "unspecified"))
    )
    (net (code "39") (name "Net-(Q2-G2)") (class "Default")
      (node (ref "Q2") (pin "4") (pinfunction "G2_4") (pintype "unspecified"))
      (node (ref "U6") (pin "1") (pinfunction "OD_1") (pintype "unspecified"))
    )
    (net (code "40") (name "Net-(U1-ADC)") (class "Default")
      (node (ref "R22") (pin "2") (pinfunction "2_2") (pintype "unspecified"))
      (node (ref "U1") (pin "2") (pinfunction "ADC_2") (pintype "unspecified"))
    )
    (net (code "41") (name "Net-(U1-EN)") (class "Default")
      (node (ref "R7") (pin "2") (pinfunction "2_2") (pintype "unspecified"))
      (node (ref "U1") (pin "3") (pinfunction "EN_3") (pintype "unspecified"))
    )
    (net (code "42") (name "Net-(U2-A0)") (class "Default")
      (node (ref "R3") (pin "1") (pinfunction "1_1") (pintype "unspecified"))
      (node (ref "U2") (pin "1") (pinfunction "A0_1") (pintype "unspecified"))
    )
    (net (code "43") (name "Net-(U2-A1)") (class "Default")
      (node (ref "R4") (pin "1") (pinfunction "1_1") (pintype "unspecified"))
      (node (ref "U2") (pin "2") (pinfunction "A1_2") (pintype "unspecified"))
    )
    (net (code "44") (name "Net-(U2-A2)") (class "Default")
      (node (ref "R5") (pin "2") (pinfunction "2_2") (pintype "unspecified"))
      (node (ref "U2") (pin "21") (pinfunction "A2_21") (pintype "unspecified"))
    )
    (net (code "45") (name "Net-(U2-RESET#)") (class "Default")
      (node (ref "R1") (pin "2") (pinfunction "2_2") (pintype "unspecified"))
      (node (ref "U2") (pin "3") (pinfunction "RESET#_3") (pintype "unspecified"))
    )
    (net (code "46") (name "Net-(U4-RXD)") (class "Default")
      (node (ref "R21") (pin "2") (pinfunction "2_2") (pintype "unspecified"))
      (node (ref "U4") (pin "3") (pinfunction "RXD_3") (pintype "unspecified"))
    )
    (net (code "47") (name "Net-(U6-CSI)") (class "Default")
      (node (ref "R13") (pin "1") (pinfunction "1_1") (pintype "unspecified"))
      (node (ref "U6") (pin "2") (pinfunction "CSI_2") (pintype "unspecified"))
    )
    (net (code "48") (name "Net-(U6-VDD)") (class "Default")
      (node (ref "C13") (pin "1") (pinfunction "1_1") (pintype "unspecified"))
      (node (ref "R11") (pin "1") (pinfunction "1_1") (pintype "unspecified"))
      (node (ref "U6") (pin "5") (pinfunction "VDD_5") (pintype "unspecified"))
    )
    (net (code "49") (name "Net-(U8-CE)") (class "Default")
      (node (ref "C14") (pin "1") (pinfunction "1_1") (pintype "unspecified"))
      (node (ref "C15") (pin "2") (pinfunction "2_2") (pintype "unspecified"))
      (node (ref "LED1") (pin "1") (pinfunction "1_1") (pintype "unspecified"))
      (node (ref "LED4") (pin "1") (pinfunction "1_1") (pintype "unspecified"))
      (node (ref "U8") (pin "4") (pinfunction "VCC_4") (pintype "unspecified"))
      (node (ref "U8") (pin "8") (pinfunction "CE_8") (pintype "unspecified"))
    )
    (net (code "50") (name "Net-(U8-CHRG#)") (class "Default")
      (node (ref "R14") (pin "2") (pinfunction "2_2") (pintype "unspecified"))
      (node (ref "U8") (pin "7") (pinfunction "CHRG#_7") (pintype "unspecified"))
    )
    (net (code "51") (name "Net-(U8-PROG)") (class "Default")
      (node (ref "R16") (pin "1") (pinfunction "1_1") (pintype "unspecified"))
      (node (ref "U8") (pin "2") (pinfunction "PROG_2") (pintype "unspecified"))
    )
    (net (code "52") (name "Net-(U8-STDBY#)") (class "Default")
      (node (ref "R15") (pin "2") (pinfunction "2_2") (pintype "unspecified"))
      (node (ref "U8") (pin "6") (pinfunction "STDBY#_6") (pintype "unspecified"))
    )
    (net (code "53") (name "Net-(USB1-CC1)") (class "Default")
      (node (ref "R9") (pin "1") (pinfunction "1_1") (pintype "unspecified"))
      (node (ref "USB1") (pin "A5") (pinfunction "CC1_A5") (pintype "unspecified"))
    )
    (net (code "54") (name "Net-(USB1-CC2)") (class "Default")
      (node (ref "R8") (pin "2") (pinfunction "2_2") (pintype "unspecified"))
      (node (ref "USB1") (pin "B5") (pinfunction "CC2_B5") (pintype "unspecified"))
    )
    (net (code "55") (name "RST") (class "Default")
      (node (ref "C19") (pin "1") (pinfunction "1_1") (pintype "unspecified"))
      (node (ref "Q1") (pin "6") (pinfunction "C_6") (pintype "unspecified"))
      (node (ref "SW2") (pin "2") (pinfunction "2_2") (pintype "unspecified"))
      (node (ref "U1") (pin "1") (pinfunction "RST_1") (pintype "unspecified"))
    )
    (net (code "56") (name "RTS") (class "Default")
      (node (ref "Q1") (pin "1") (pinfunction "E_1") (pintype "unspecified"))
      (node (ref "Q1") (pin "5") (pinfunction "B_5") (pintype "unspecified"))
      (node (ref "U4") (pin "14") (pinfunction "RTS#_14") (pintype "unspecified"))
    )
    (net (code "57") (name "RX") (class "Default")
      (node (ref "U1") (pin "15") (pinfunction "RXD0_15") (pintype "unspecified"))
      (node (ref "U4") (pin "2") (pinfunction "TXD_2") (pintype "unspecified"))
    )
    (net (code "58") (name "SC0") (class "Default")
      (node (ref "R2") (pin "2") (pinfunction "2_2") (pintype "unspecified"))
      (node (ref "RJ1") (pin "3") (pinfunction "3_3") (pintype "unspecified"))
      (node (ref "U2") (pin "5") (pinfunction "SC0_5") (pintype "unspecified"))
      (node (ref "U9") (pin "5") (pinfunction "BUS2_5") (pintype "unspecified"))
    )
    (net (code "59") (name "SC1") (class "Default")
      (node (ref "R25") (pin "2") (pinfunction "2_2") (pintype "unspecified"))
      (node (ref "RJ2") (pin "6") (pinfunction "6_6") (pintype "unspecified"))
      (node (ref "U10") (pin "5") (pinfunction "BUS2_5") (pintype "unspecified"))
      (node (ref "U2") (pin "7") (pinfunction "SC1_7") (pintype "unspecified"))
    )
    (net (code "60") (name "SC2") (class "Default")
      (node (ref "R27") (pin "2") (pinfunction "2_2") (pintype "unspecified"))
      (node (ref "RJ4") (pin "6") (pinfunction "6_6") (pintype "unspecified"))
      (node (ref "U11") (pin "5") (pinfunction "BUS2_5") (pintype "unspecified"))
      (node (ref "U2") (pin "9") (pinfunction "SC2_9") (pintype "unspecified"))
    )
    (net (code "61") (name "SC3") (class "Default")
      (node (ref "R29") (pin "2") (pinfunction "2_2") (pintype "unspecified"))
      (node (ref "RJ3") (pin "6") (pinfunction "6_6") (pintype "unspecified"))
      (node (ref "U12") (pin "5") (pinfunction "BUS2_5") (pintype "unspecified"))
      (node (ref "U2") (pin "11") (pinfunction "SC3_11") (pintype "unspecified"))
    )
    (net (code "62") (name "SC4") (class "Default")
      (node (ref "R31") (pin "2") (pinfunction "2_2") (pintype "unspecified"))
      (node (ref "RJ8") (pin "6") (pinfunction "6_6") (pintype "unspecified"))
      (node (ref "U13") (pin "5") (pinfunction "BUS2_5") (pintype "unspecified"))
      (node (ref "U2") (pin "14") (pinfunction "SC4_14") (pintype "unspecified"))
    )
    (net (code "63") (name "SC5") (class "Default")
      (node (ref "R33") (pin "2") (pinfunction "2_2") (pintype "unspecified"))
      (node (ref "RJ7") (pin "6") (pinfunction "6_6") (pintype "unspecified"))
      (node (ref "U14") (pin "5") (pinfunction "BUS2_5") (pintype "unspecified"))
      (node (ref "U2") (pin "16") (pinfunction "SC5_16") (pintype "unspecified"))
    )
    (net (code "64") (name "SC6") (class "Default")
      (node (ref "R35") (pin "2") (pinfunction "2_2") (pintype "unspecified"))
      (node (ref "RJ5") (pin "6") (pinfunction "6_6") (pintype "unspecified"))
      (node (ref "U15") (pin "5") (pinfunction "BUS2_5") (pintype "unspecified"))
      (node (ref "U2") (pin "18") (pinfunction "SC6_18") (pintype "unspecified"))
    )
    (net (code "65") (name "SC7") (class "Default")
      (node (ref "R37") (pin "2") (pinfunction "2_2") (pintype "unspecified"))
      (node (ref "RJ6") (pin "6") (pinfunction "6_6") (pintype "unspecified"))
      (node (ref "U16") (pin "5") (pinfunction "BUS2_5") (pintype "unspecified"))
      (node (ref "U2") (pin "20") (pinfunction "SC7_20") (pintype "unspecified"))
    )
    (net (code "66") (name "SCL") (class "Default")
      (node (ref "J1") (pin "3") (pinfunction "3_3") (pintype "unspecified"))
      (node (ref "R10") (pin "2") (pinfunction "2_2") (pintype "unspecified"))
      (node (ref "R18") (pin "1") (pinfunction "1_1") (pintype "unspecified"))
      (node (ref "U1") (pin "14") (pinfunction "GPIO5_14") (pintype "unspecified"))
      (node (ref "U2") (pin "22") (pinfunction "SCL_22") (pintype "unspecified"))
      (node (ref "U3") (pin "5") (pinfunction "BUS2_5") (pintype "unspecified"))
      (node (ref "U5") (pin "8") (pinfunction "SCK_8") (pintype "unspecified"))
    )
    (net (code "67") (name "SD0") (class "Default")
      (node (ref "R23") (pin "2") (pinfunction "2_2") (pintype "unspecified"))
      (node (ref "RJ1") (pin "6") (pinfunction "6_6") (pintype "unspecified"))
      (node (ref "U2") (pin "4") (pinfunction "SD0_4") (pintype "unspecified"))
      (node (ref "U9") (pin "4") (pinfunction "BUS1_4") (pintype "unspecified"))
    )
    (net (code "68") (name "SD1") (class "Default")
      (node (ref "R24") (pin "2") (pinfunction "2_2") (pintype "unspecified"))
      (node (ref "RJ2") (pin "3") (pinfunction "3_3") (pintype "unspecified"))
      (node (ref "U10") (pin "4") (pinfunction "BUS1_4") (pintype "unspecified"))
      (node (ref "U2") (pin "6") (pinfunction "SD1_6") (pintype "unspecified"))
    )
    (net (code "69") (name "SD2") (class "Default")
      (node (ref "R26") (pin "2") (pinfunction "2_2") (pintype "unspecified"))
      (node (ref "RJ4") (pin "3") (pinfunction "3_3") (pintype "unspecified"))
      (node (ref "U11") (pin "4") (pinfunction "BUS1_4") (pintype "unspecified"))
      (node (ref "U2") (pin "8") (pinfunction "SD2_8") (pintype "unspecified"))
    )
    (net (code "70") (name "SD3") (class "Default")
      (node (ref "R28") (pin "2") (pinfunction "2_2") (pintype "unspecified"))
      (node (ref "RJ3") (pin "3") (pinfunction "3_3") (pintype "unspecified"))
      (node (ref "U12") (pin "4") (pinfunction "BUS1_4") (pintype "unspecified"))
      (node (ref "U2") (pin "10") (pinfunction "SD3_10") (pintype "unspecified"))
    )
    (net (code "71") (name "SD4") (class "Default")
      (node (ref "R30") (pin "2") (pinfunction "2_2") (pintype "unspecified"))
      (node (ref "RJ8") (pin "3") (pinfunction "3_3") (pintype "unspecified"))
      (node (ref "U13") (pin "4") (pinfunction "BUS1_4") (pintype "unspecified"))
      (node (ref "U2") (pin "13") (pinfunction "SD4_13") (pintype "unspecified"))
    )
    (net (code "72") (name "SD5") (class "Default")
      (node (ref "R32") (pin "2") (pinfunction "2_2") (pintype "unspecified"))
      (node (ref "RJ7") (pin "3") (pinfunction "3_3") (pintype "unspecified"))
      (node (ref "U14") (pin "4") (pinfunction "BUS1_4") (pintype "unspecified"))
      (node (ref "U2") (pin "15") (pinfunction "SD5_15") (pintype "unspecified"))
    )
    (net (code "73") (name "SD6") (class "Default")
      (node (ref "R34") (pin "2") (pinfunction "2_2") (pintype "unspecified"))
      (node (ref "RJ5") (pin "3") (pinfunction "3_3") (pintype "unspecified"))
      (node (ref "U15") (pin "4") (pinfunction "BUS1_4") (pintype "unspecified"))
      (node (ref "U2") (pin "17") (pinfunction "SD6_17") (pintype "unspecified"))
    )
    (net (code "74") (name "SD7") (class "Default")
      (node (ref "R36") (pin "2") (pinfunction "2_2") (pintype "unspecified"))
      (node (ref "RJ6") (pin "3") (pinfunction "3_3") (pintype "unspecified"))
      (node (ref "U16") (pin "4") (pinfunction "BUS1_4") (pintype "unspecified"))
      (node (ref "U2") (pin "19") (pinfunction "SD7_19") (pintype "unspecified"))
    )
    (net (code "75") (name "SDA") (class "Default")
      (node (ref "J1") (pin "4") (pinfunction "4_4") (pintype "unspecified"))
      (node (ref "R12") (pin "2") (pinfunction "2_2") (pintype "unspecified"))
      (node (ref "R17") (pin "2") (pinfunction "2_2") (pintype "unspecified"))
      (node (ref "U1") (pin "13") (pinfunction "GPIO4_13") (pintype "unspecified"))
      (node (ref "U2") (pin "23") (pinfunction "SDA_23") (pintype "unspecified"))
      (node (ref "U3") (pin "4") (pinfunction "BUS1_4") (pintype "unspecified"))
      (node (ref "U5") (pin "9") (pinfunction "SDA_9") (pintype "unspecified"))
    )
    (net (code "76") (name "TX") (class "Default")
      (node (ref "R21") (pin "1") (pinfunction "1_1") (pintype "unspecified"))
      (node (ref "U1") (pin "16") (pinfunction "TXD0_16") (pintype "unspecified"))
    )
    (net (code "77") (name "unconnected-(Q2-D12-Pad2)") (class "Default")
      (node (ref "Q2") (pin "2") (pinfunction "D12_2") (pintype "unspecified+no_connect"))
    )
    (net (code "78") (name "unconnected-(Q2-D12-Pad5)") (class "Default")
      (node (ref "Q2") (pin "5") (pinfunction "D12_5") (pintype "unspecified+no_connect"))
    )
    (net (code "79") (name "unconnected-(Q3-NC-Pad4)") (class "Default")
      (node (ref "Q3") (pin "4") (pinfunction "NC_4") (pintype "unspecified+no_connect"))
    )
    (net (code "80") (name "unconnected-(RJ1-Pad2)") (class "Default")
      (node (ref "RJ1") (pin "2") (pinfunction "2_2") (pintype "unspecified+no_connect"))
    )
    (net (code "81") (name "unconnected-(RJ1-Pad7)") (class "Default")
      (node (ref "RJ1") (pin "7") (pinfunction "7_7") (pintype "unspecified+no_connect"))
    )
    (net (code "82") (name "unconnected-(RJ2-Pad2)") (class "Default")
      (node (ref "RJ2") (pin "2") (pinfunction "2_2") (pintype "unspecified+no_connect"))
    )
    (net (code "83") (name "unconnected-(RJ2-Pad7)") (class "Default")
      (node (ref "RJ2") (pin "7") (pinfunction "7_7") (pintype "unspecified+no_connect"))
    )
    (net (code "84") (name "unconnected-(RJ3-Pad2)") (class "Default")
      (node (ref "RJ3") (pin "2") (pinfunction "2_2") (pintype "unspecified+no_connect"))
    )
    (net (code "85") (name "unconnected-(RJ3-Pad5)") (class "Default")
      (node (ref "RJ3") (pin "5") (pinfunction "5_5") (pintype "unspecified+no_connect"))
    )
    (net (code "86") (name "unconnected-(RJ3-Pad7)") (class "Default")
      (node (ref "RJ3") (pin "7") (pinfunction "7_7") (pintype "unspecified+no_connect"))
    )
    (net (code "87") (name "unconnected-(RJ4-Pad2)") (class "Default")
      (node (ref "RJ4") (pin "2") (pinfunction "2_2") (pintype "unspecified+no_connect"))
    )
    (net (code "88") (name "unconnected-(RJ4-Pad7)") (class "Default")
      (node (ref "RJ4") (pin "7") (pinfunction "7_7") (pintype "unspecified+no_connect"))
    )
    (net (code "89") (name "unconnected-(RJ5-Pad2)") (class "Default")
      (node (ref "RJ5") (pin "2") (pinfunction "2_2") (pintype "unspecified+no_connect"))
    )
    (net (code "90") (name "unconnected-(RJ5-Pad7)") (class "Default")
      (node (ref "RJ5") (pin "7") (pinfunction "7_7") (pintype "unspecified+no_connect"))
    )
    (net (code "91") (name "unconnected-(RJ6-Pad2)") (class "Default")
      (node (ref "RJ6") (pin "2") (pinfunction "2_2") (pintype "unspecified+no_connect"))
    )
    (net (code "92") (name "unconnected-(RJ6-Pad7)") (class "Default")
      (node (ref "RJ6") (pin "7") (pinfunction "7_7") (pintype "unspecified+no_connect"))
    )
    (net (code "93") (name "unconnected-(RJ7-Pad2)") (class "Default")
      (node (ref "RJ7") (pin "2") (pinfunction "2_2") (pintype "unspecified+no_connect"))
    )
    (net (code "94") (name "unconnected-(RJ7-Pad7)") (class "Default")
      (node (ref "RJ7") (pin "7") (pinfunction "7_7") (pintype "unspecified+no_connect"))
    )
    (net (code "95") (name "unconnected-(RJ8-Pad2)") (class "Default")
      (node (ref "RJ8") (pin "2") (pinfunction "2_2") (pintype "unspecified+no_connect"))
    )
    (net (code "96") (name "unconnected-(RJ8-Pad7)") (class "Default")
      (node (ref "RJ8") (pin "7") (pinfunction "7_7") (pintype "unspecified+no_connect"))
    )
    (net (code "97") (name "unconnected-(SW2-Pad1)") (class "Default")
      (node (ref "SW2") (pin "1") (pinfunction "1_1") (pintype "unspecified+no_connect"))
    )
    (net (code "98") (name "unconnected-(SW2-Pad4)") (class "Default")
      (node (ref "SW2") (pin "4") (pinfunction "4_4") (pintype "unspecified+no_connect"))
    )
    (net (code "99") (name "unconnected-(U1-CS0-Pad17)") (class "Default")
      (node (ref "U1") (pin "17") (pinfunction "CS0_17") (pintype "unspecified+no_connect"))
    )
    (net (code "100") (name "unconnected-(U1-GPIO9-Pad19)") (class "Default")
      (node (ref "U1") (pin "19") (pinfunction "GPIO9_19") (pintype "unspecified+no_connect"))
    )
    (net (code "101") (name "unconnected-(U1-GPIO10-Pad20)") (class "Default")
      (node (ref "U1") (pin "20") (pinfunction "GPIO10_20") (pintype "unspecified+no_connect"))
    )
    (net (code "102") (name "unconnected-(U1-GPIO16-Pad4)") (class "Default")
      (node (ref "U1") (pin "4") (pinfunction "GPIO16_4") (pintype "unspecified+no_connect"))
    )
    (net (code "103") (name "unconnected-(U1-MISO-Pad18)") (class "Default")
      (node (ref "U1") (pin "18") (pinfunction "MISO_18") (pintype "unspecified+no_connect"))
    )
    (net (code "104") (name "unconnected-(U1-MOSI-Pad21)") (class "Default")
      (node (ref "U1") (pin "21") (pinfunction "MOSI_21") (pintype "unspecified+no_connect"))
    )
    (net (code "105") (name "unconnected-(U1-SCLK-Pad22)") (class "Default")
      (node (ref "U1") (pin "22") (pinfunction "SCLK_22") (pintype "unspecified+no_connect"))
    )
    (net (code "106") (name "unconnected-(U3-NC-Pad2)") (class "Default")
      (node (ref "U3") (pin "2") (pinfunction "NC_2") (pintype "unspecified+no_connect"))
    )
    (net (code "107") (name "unconnected-(U4-CTS#-Pad9)") (class "Default")
      (node (ref "U4") (pin "9") (pinfunction "CTS#_9") (pintype "unspecified+no_connect"))
    )
    (net (code "108") (name "unconnected-(U4-DCD#-Pad12)") (class "Default")
      (node (ref "U4") (pin "12") (pinfunction "DCD#_12") (pintype "unspecified+no_connect"))
    )
    (net (code "109") (name "unconnected-(U4-DSR#-Pad10)") (class "Default")
      (node (ref "U4") (pin "10") (pinfunction "DSR#_10") (pintype "unspecified+no_connect"))
    )
    (net (code "110") (name "unconnected-(U4-NC.-Pad7)") (class "Default")
      (node (ref "U4") (pin "7") (pinfunction "NC._7") (pintype "unspecified+no_connect"))
    )
    (net (code "111") (name "unconnected-(U4-NC.-Pad8)") (class "Default")
      (node (ref "U4") (pin "8") (pinfunction "NC._8") (pintype "unspecified+no_connect"))
    )
    (net (code "112") (name "unconnected-(U4-R232-Pad15)") (class "Default")
      (node (ref "U4") (pin "15") (pinfunction "R232_15") (pintype "unspecified+no_connect"))
    )
    (net (code "113") (name "unconnected-(U4-RI#-Pad11)") (class "Default")
      (node (ref "U4") (pin "11") (pinfunction "RI#_11") (pintype "unspecified+no_connect"))
    )
    (net (code "114") (name "unconnected-(U5-NC-Pad7)") (class "Default")
      (node (ref "U5") (pin "7") (pinfunction "NC_7") (pintype "unspecified+no_connect"))
    )
    (net (code "115") (name "unconnected-(U5-NC-Pad10)") (class "Default")
      (node (ref "U5") (pin "10") (pinfunction "NC_10") (pintype "unspecified+no_connect"))
    )
    (net (code "116") (name "unconnected-(U6-TD-Pad4)") (class "Default")
      (node (ref "U6") (pin "4") (pinfunction "TD_4") (pintype "unspecified+no_connect"))
    )
    (net (code "117") (name "unconnected-(U8-EP-Pad9)") (class "Default")
      (node (ref "U8") (pin "9") (pinfunction "EP_9") (pintype "unspecified+no_connect"))
    )
    (net (code "118") (name "unconnected-(U9-NC-Pad2)") (class "Default")
      (node (ref "U9") (pin "2") (pinfunction "NC_2") (pintype "unspecified+no_connect"))
    )
    (net (code "119") (name "unconnected-(U10-NC-Pad2)") (class "Default")
      (node (ref "U10") (pin "2") (pinfunction "NC_2") (pintype "unspecified+no_connect"))
    )
    (net (code "120") (name "unconnected-(U11-NC-Pad2)") (class "Default")
      (node (ref "U11") (pin "2") (pinfunction "NC_2") (pintype "unspecified+no_connect"))
    )
    (net (code "121") (name "unconnected-(U12-NC-Pad2)") (class "Default")
      (node (ref "U12") (pin "2") (pinfunction "NC_2") (pintype "unspecified+no_connect"))
    )
    (net (code "122") (name "unconnected-(U13-NC-Pad2)") (class "Default")
      (node (ref "U13") (pin "2") (pinfunction "NC_2") (pintype "unspecified+no_connect"))
    )
    (net (code "123") (name "unconnected-(U14-NC-Pad2)") (class "Default")
      (node (ref "U14") (pin "2") (pinfunction "NC_2") (pintype "unspecified+no_connect"))
    )
    (net (code "124") (name "unconnected-(U15-NC-Pad2)") (class "Default")
      (node (ref "U15") (pin "2") (pinfunction "NC_2") (pintype "unspecified+no_connect"))
    )
    (net (code "125") (name "unconnected-(U16-NC-Pad2)") (class "Default")
      (node (ref "U16") (pin "2") (pinfunction "NC_2") (pintype "unspecified+no_connect"))
    )
    (net (code "126") (name "unconnected-(USB1-SBU1-PadA8)") (class "Default")
      (node (ref "USB1") (pin "A8") (pinfunction "SBU1_A8") (pintype "unspecified+no_connect"))
    )
    (net (code "127") (name "unconnected-(USB1-SBU2-PadB8)") (class "Default")
      (node (ref "USB1") (pin "B8") (pinfunction "SBU2_B8") (pintype "unspecified+no_connect"))
    )
  )
)
